# PWM_CONTROLLER_nverter_540VDC_V2.net
KiCad netlist of a schematic drawn in Altium Designer
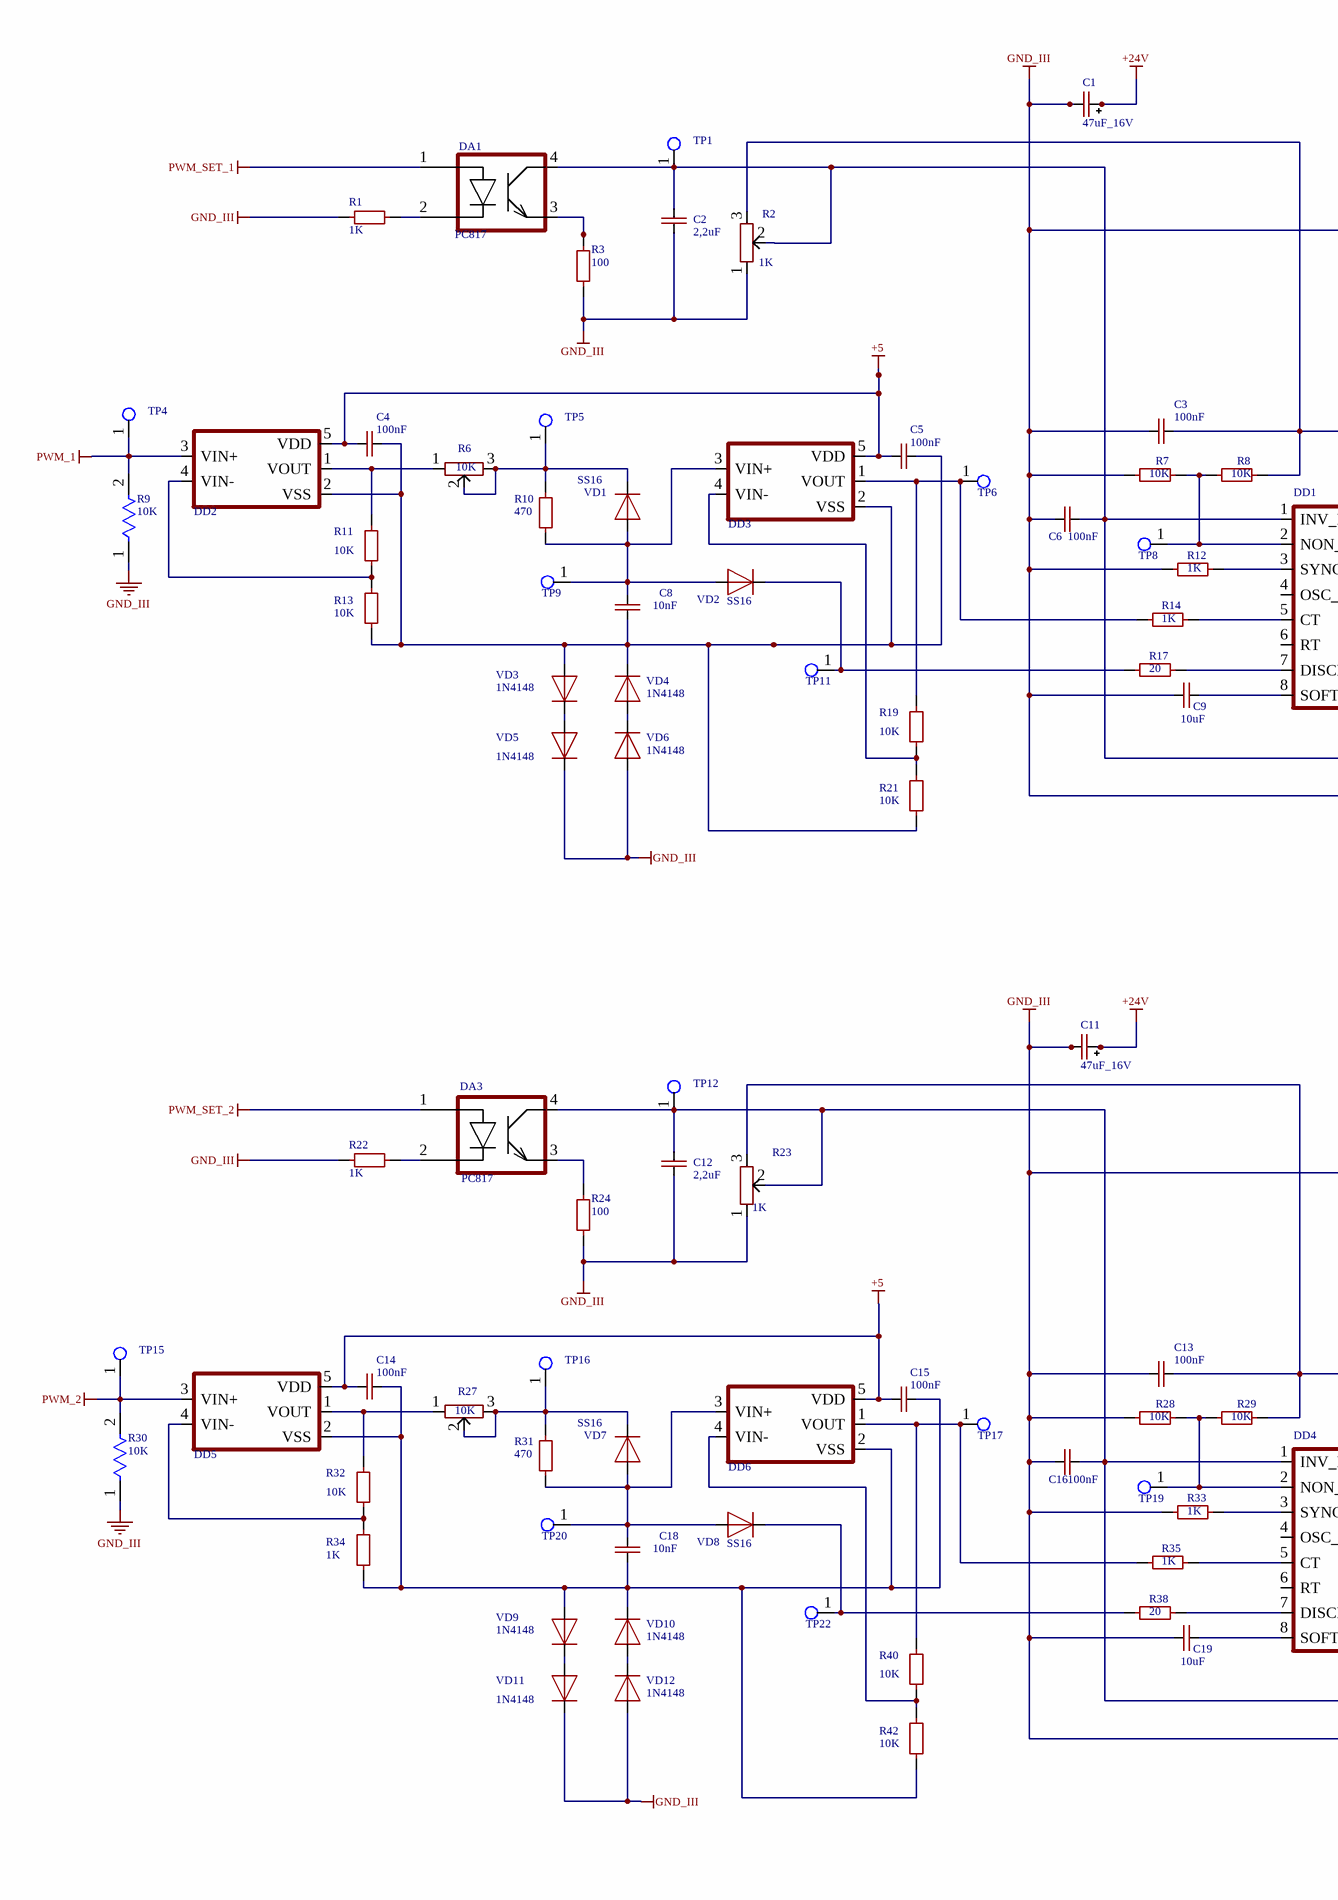
[diagram p0: PWM_CONTROLLER_nverter_540VDC_V2.SchDoc, top left]
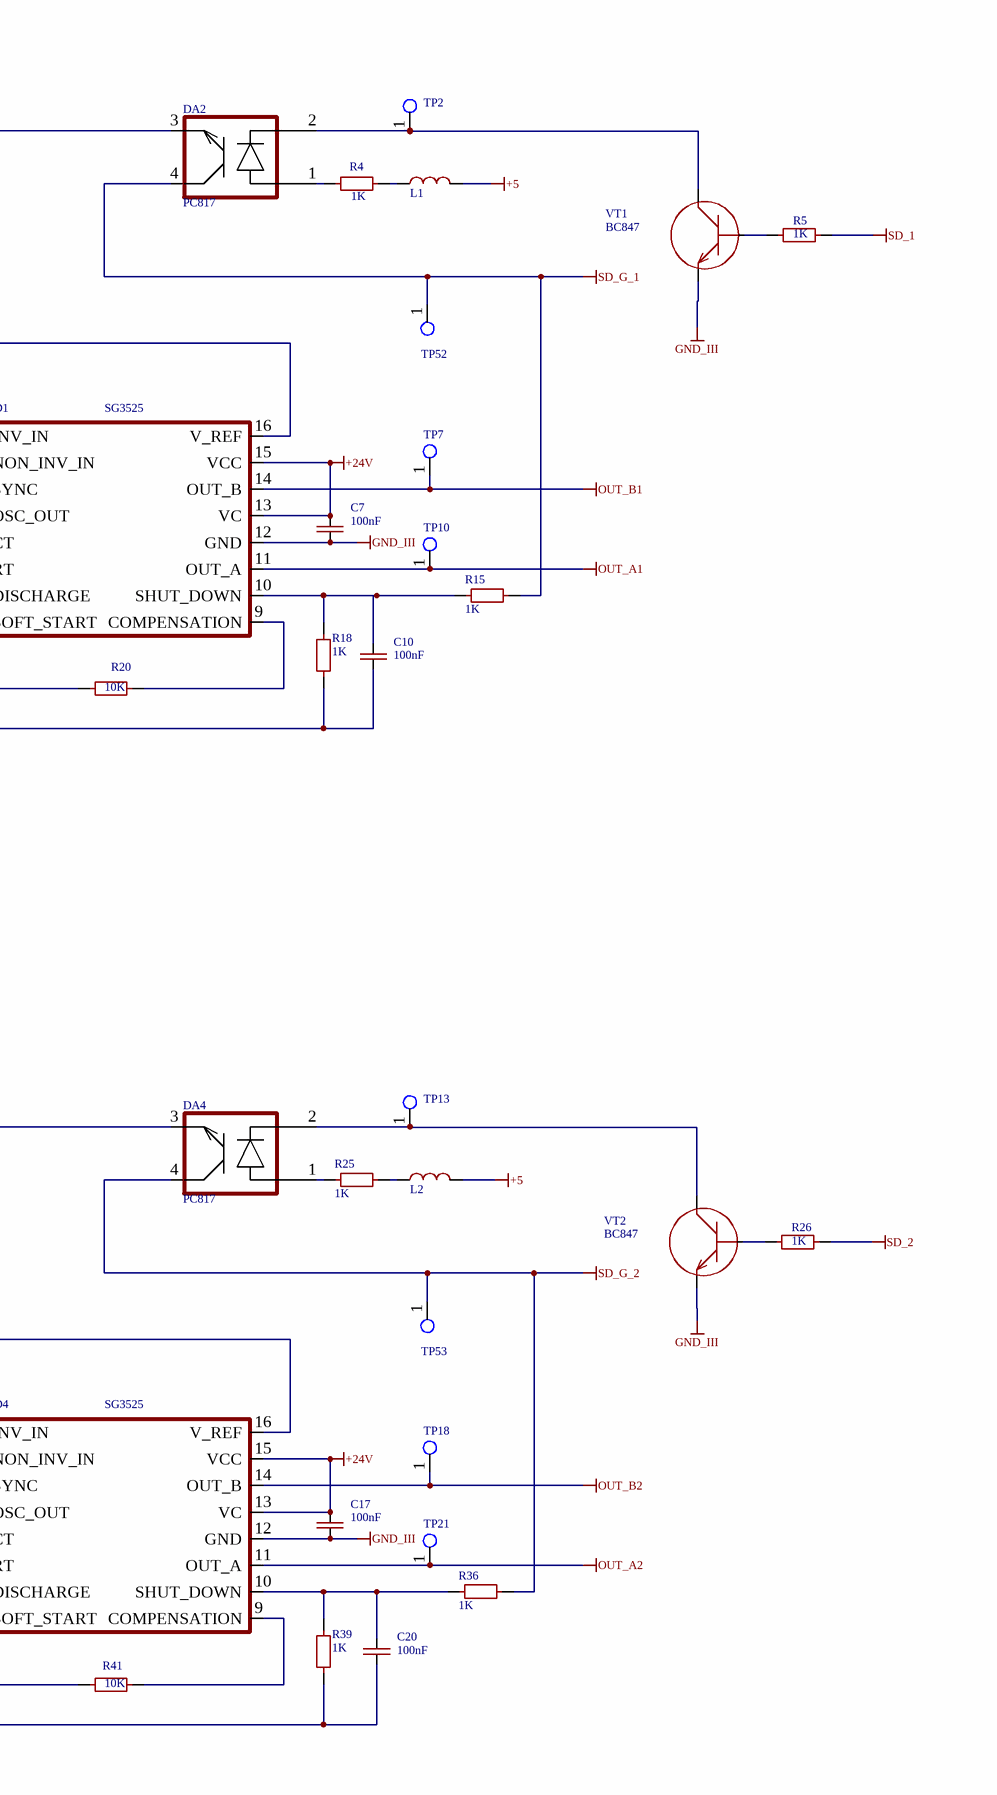
[diagram p1: PWM_CONTROLLER_nverter_540VDC_V2.SchDoc, top right]
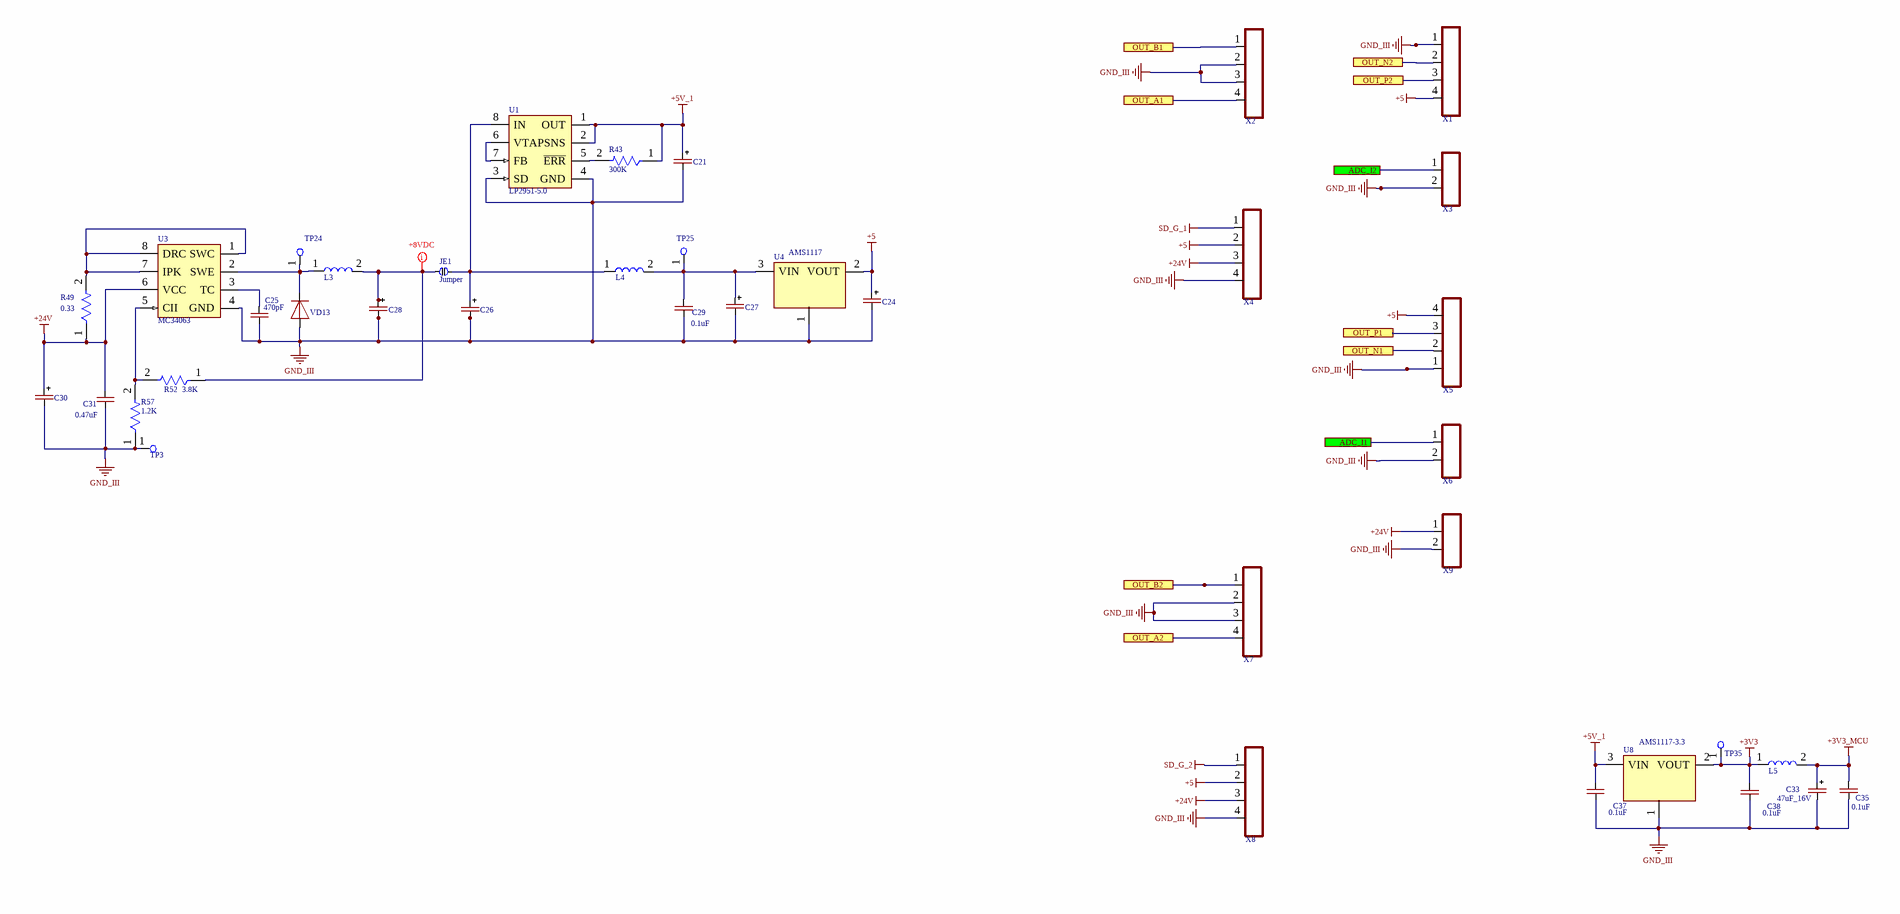
[diagram p2: PWM_CONTROLLER_nverter_540VDC_V2.SchDoc, bottom left]
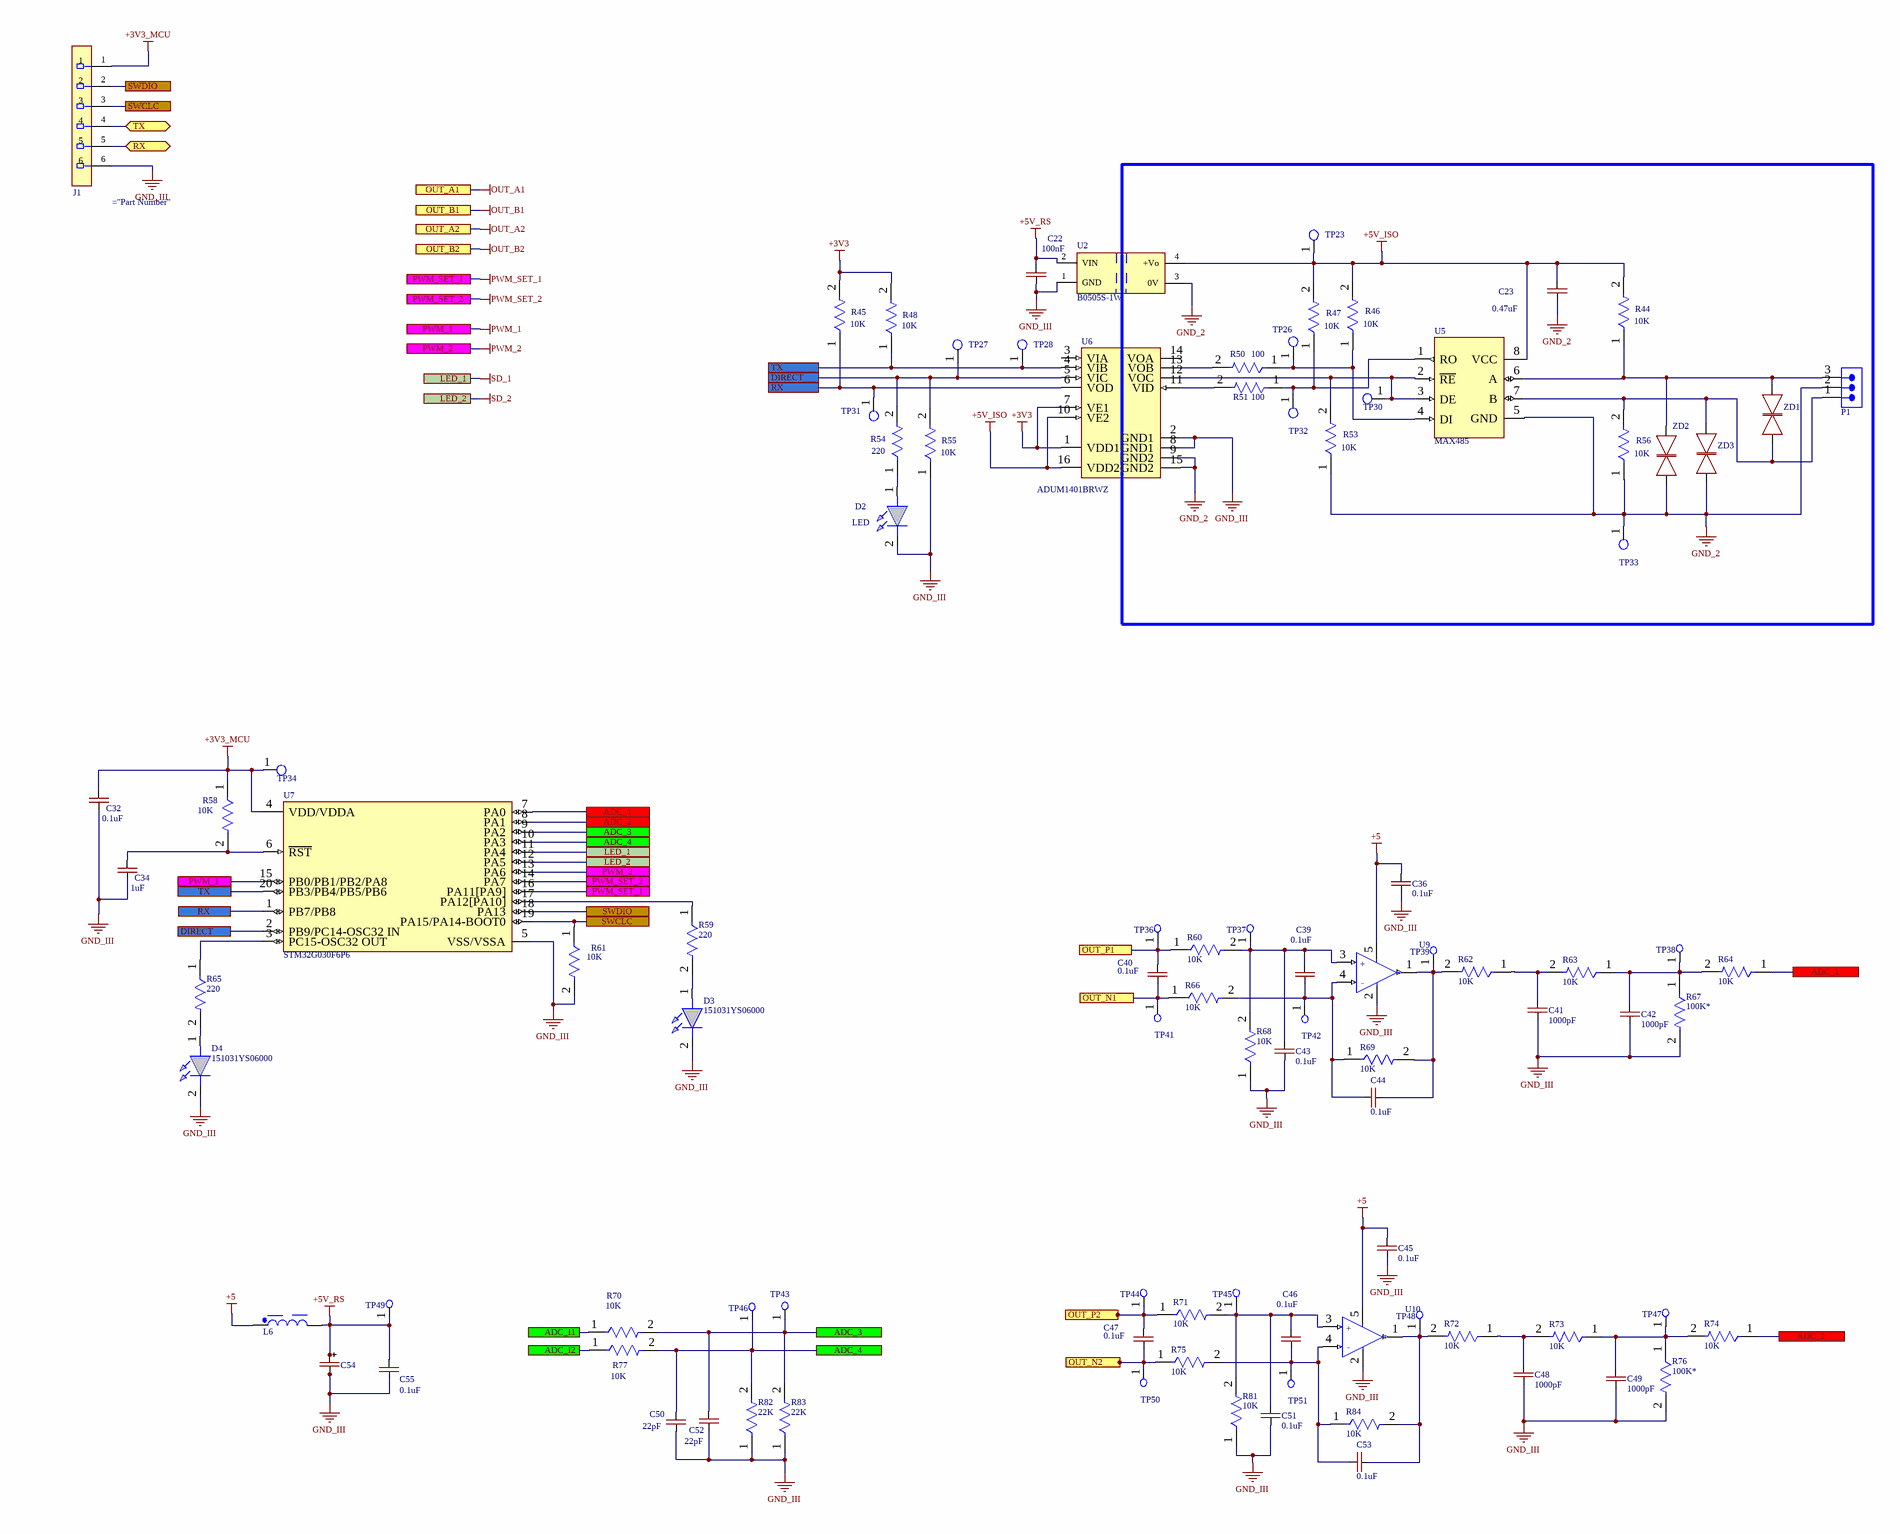
[diagram p3: PWM_CONTROLLER_nverter_540VDC_V2.SchDoc, bottom right]

(export (version "E")
  (design (tool "Eeschema 10.0.6"))
  (components
    (comp (ref "C1")
      (value "47uF_16V")
      (footprint "CAP-TAN-D")
      (libsource (lib "PASSIVE_COMPONENTS") (part "CAP-POLAR"))
    )
    (comp (ref "C2")
      (value "2,2uF")
      (footprint "CAP-0805")
      (libsource (lib "PAS_COMPONENTS") (part "CAP-NON-POLAR"))
    )
    (comp (ref "C3")
      (value "100nF")
      (footprint "CAP-0805")
      (libsource (lib "PAS_COMPONENTS") (part "CAP-NON-POLAR"))
    )
    (comp (ref "C4")
      (value "100nF")
      (footprint "CAP-0805")
      (libsource (lib "PAS_COMPONENTS") (part "CAP-NON-POLAR"))
    )
    (comp (ref "C5")
      (value "100nF")
      (footprint "CAP-0805")
      (libsource (lib "PAS_COMPONENTS") (part "CAP-NON-POLAR"))
    )
    (comp (ref "C6")
      (value "100nF")
      (footprint "CAP-0805")
      (libsource (lib "PAS_COMPONENTS") (part "CAP-NON-POLAR"))
    )
    (comp (ref "C7")
      (value "100nF")
      (footprint "CAP-0805")
      (libsource (lib "PAS_COMPONENTS") (part "CAP-NON-POLAR"))
    )
    (comp (ref "C8")
      (value "10nF")
      (footprint "CAP-0805")
      (libsource (lib "PAS_COMPONENTS") (part "CAP-NON-POLAR"))
    )
    (comp (ref "C9")
      (value "10uF")
      (footprint "CAP-0805")
      (libsource (lib "PAS_COMPONENTS") (part "CAP-NON-POLAR"))
    )
    (comp (ref "C10")
      (value "100nF")
      (footprint "CAP-0805")
      (libsource (lib "PAS_COMPONENTS") (part "CAP-NON-POLAR"))
    )
    (comp (ref "C11")
      (value "47uF_16V")
      (footprint "CAP-TAN-D")
      (libsource (lib "PASSIVE_COMPONENTS") (part "CAP-POLAR"))
    )
    (comp (ref "C12")
      (value "2,2uF")
      (footprint "CAP-0805")
      (libsource (lib "PAS_COMPONENTS") (part "CAP-NON-POLAR"))
    )
    (comp (ref "C13")
      (value "100nF")
      (footprint "CAP-0805")
      (libsource (lib "PAS_COMPONENTS") (part "CAP-NON-POLAR"))
    )
    (comp (ref "C14")
      (value "100nF")
      (footprint "CAP-0805")
      (libsource (lib "PAS_COMPONENTS") (part "CAP-NON-POLAR"))
    )
    (comp (ref "C15")
      (value "100nF")
      (footprint "CAP-0805")
      (libsource (lib "PAS_COMPONENTS") (part "CAP-NON-POLAR"))
    )
    (comp (ref "C16")
      (value "100nF")
      (footprint "CAP-0805")
      (libsource (lib "PAS_COMPONENTS") (part "CAP-NON-POLAR"))
    )
    (comp (ref "C17")
      (value "100nF")
      (footprint "CAP-0805")
      (libsource (lib "PAS_COMPONENTS") (part "CAP-NON-POLAR"))
    )
    (comp (ref "C18")
      (value "10nF")
      (footprint "CAP-0805")
      (libsource (lib "PAS_COMPONENTS") (part "CAP-NON-POLAR"))
    )
    (comp (ref "C19")
      (value "10uF")
      (footprint "CAP-0805")
      (libsource (lib "PAS_COMPONENTS") (part "CAP-NON-POLAR"))
    )
    (comp (ref "C20")
      (value "100nF")
      (footprint "CAP-0805")
      (libsource (lib "PAS_COMPONENTS") (part "CAP-NON-POLAR"))
    )
    (comp (ref "C21")
      (value "CAP-POLAR")
      (footprint "CAP-TAN-C")
      (libsource (lib "PAS_COMPONENTS") (part "CAP-POLAR"))
    )
    (comp (ref "C22")
      (value "100nF")
      (footprint "CAP-0805")
      (libsource (lib "PASSIVE_COMPONENTS") (part "CAP-NON-POLAR"))
    )
    (comp (ref "C23")
      (value "0.47uF")
      (footprint "CAP-0805")
      (libsource (lib "PASSIVE_COMPONENTS") (part "CAP-NON-POLAR"))
    )
    (comp (ref "C24")
      (value "CAP-POLAR")
      (footprint "CAP-TAN-C")
      (libsource (lib "PAS_COMPONENTS") (part "CAP-POLAR"))
    )
    (comp (ref "C25")
      (value "470pF")
      (footprint "CAP-0805")
      (libsource (lib "PASSIVE_COMPONENTS") (part "CAP-NON-POLAR"))
    )
    (comp (ref "C26")
      (value "CAP-POLAR")
      (footprint "CAP-TAN-C")
      (libsource (lib "PAS_COMPONENTS") (part "CAP-POLAR"))
    )
    (comp (ref "C27")
      (value "CAP-POLAR")
      (footprint "CAP-TAN-C")
      (libsource (lib "PAS_COMPONENTS") (part "CAP-POLAR"))
    )
    (comp (ref "C28")
      (value "CAP-POLAR")
      (footprint "CAP-TAN-C")
      (libsource (lib "PAS_COMPONENTS") (part "CAP-POLAR"))
    )
    (comp (ref "C29")
      (value "0.1uF")
      (footprint "CAP-0805")
      (libsource (lib "PASSIVE_COMPONENTS") (part "CAP-NON-POLAR"))
    )
    (comp (ref "C30")
      (value "CAP-POLAR")
      (footprint "CAP-TAN-C")
      (libsource (lib "PAS_COMPONENTS") (part "CAP-POLAR"))
    )
    (comp (ref "C31")
      (value "0.47uF")
      (footprint "CAP-0805")
      (libsource (lib "PASSIVE_COMPONENTS") (part "CAP-NON-POLAR"))
    )
    (comp (ref "C32")
      (value "0.1uF")
      (footprint "CAP-0805")
      (libsource (lib "PASSIVE_COMPONENTS") (part "CAP-NON-POLAR"))
    )
    (comp (ref "C33")
      (value "47uF_16V")
      (footprint "CAP-TAN-D")
      (libsource (lib "PASSIVE_COMPONENTS") (part "CAP-POLAR"))
    )
    (comp (ref "C34")
      (value "1uF")
      (footprint "CAP-0805")
      (libsource (lib "PASSIVE_COMPONENTS") (part "CAP-NON-POLAR"))
    )
    (comp (ref "C35")
      (value "0.1uF")
      (footprint "CAP-0805")
      (libsource (lib "PASSIVE_COMPONENTS") (part "CAP-NON-POLAR"))
    )
    (comp (ref "C36")
      (value "0.1uF")
      (footprint "CAP-0805")
      (libsource (lib "PASSIVE_COMPONENTS") (part "CAP-NON-POLAR"))
    )
    (comp (ref "C37")
      (value "0.1uF")
      (footprint "CAP-0805")
      (libsource (lib "PASSIVE_COMPONENTS") (part "CAP-NON-POLAR"))
    )
    (comp (ref "C38")
      (value "0.1uF")
      (footprint "CAP-0805")
      (libsource (lib "PASSIVE_COMPONENTS") (part "CAP-NON-POLAR"))
    )
    (comp (ref "C39")
      (value "0.1uF")
      (footprint "CAP-0805")
      (libsource (lib "PASSIVE_COMPONENTS") (part "CAP-NON-POLAR"))
    )
    (comp (ref "C40")
      (value "0.1uF")
      (footprint "CAP-0805")
      (libsource (lib "PASSIVE_COMPONENTS") (part "CAP-NON-POLAR"))
    )
    (comp (ref "C41")
      (value "1000pF")
      (footprint "CAP-0805")
      (libsource (lib "PASSIVE_COMPONENTS") (part "CAP-NON-POLAR"))
    )
    (comp (ref "C42")
      (value "1000pF")
      (footprint "CAP-0805")
      (libsource (lib "PASSIVE_COMPONENTS") (part "CAP-NON-POLAR"))
    )
    (comp (ref "C43")
      (value "0.1uF")
      (footprint "CAP-0805")
      (libsource (lib "PASSIVE_COMPONENTS") (part "CAP-NON-POLAR"))
    )
    (comp (ref "C44")
      (value "0.1uF")
      (footprint "CAP-0805")
      (libsource (lib "PASSIVE_COMPONENTS") (part "CAP-NON-POLAR"))
    )
    (comp (ref "C45")
      (value "0.1uF")
      (footprint "CAP-0805")
      (libsource (lib "PASSIVE_COMPONENTS") (part "CAP-NON-POLAR"))
    )
    (comp (ref "C46")
      (value "0.1uF")
      (footprint "CAP-0805")
      (libsource (lib "PASSIVE_COMPONENTS") (part "CAP-NON-POLAR"))
    )
    (comp (ref "C47")
      (value "0.1uF")
      (footprint "CAP-0805")
      (libsource (lib "PASSIVE_COMPONENTS") (part "CAP-NON-POLAR"))
    )
    (comp (ref "C48")
      (value "1000pF")
      (footprint "CAP-0805")
      (libsource (lib "PASSIVE_COMPONENTS") (part "CAP-NON-POLAR"))
    )
    (comp (ref "C49")
      (value "1000pF")
      (footprint "CAP-0805")
      (libsource (lib "PASSIVE_COMPONENTS") (part "CAP-NON-POLAR"))
    )
    (comp (ref "C50")
      (value "22pF")
      (footprint "CAP-0805")
      (libsource (lib "PASSIVE_COMPONENTS") (part "CAP-NON-POLAR"))
    )
    (comp (ref "C51")
      (value "0.1uF")
      (footprint "CAP-0805")
      (libsource (lib "PASSIVE_COMPONENTS") (part "CAP-NON-POLAR"))
    )
    (comp (ref "C52")
      (value "22pF")
      (footprint "CAP-0805")
      (libsource (lib "PASSIVE_COMPONENTS") (part "CAP-NON-POLAR"))
    )
    (comp (ref "C53")
      (value "0.1uF")
      (footprint "CAP-0805")
      (libsource (lib "PASSIVE_COMPONENTS") (part "CAP-NON-POLAR"))
    )
    (comp (ref "C54")
      (value "CAP-POLAR")
      (footprint "CAP-TAN-C")
      (libsource (lib "PAS_COMPONENTS") (part "CAP-POLAR"))
    )
    (comp (ref "C55")
      (value "0.1uF")
      (footprint "CAP-0805")
      (libsource (lib "PASSIVE_COMPONENTS") (part "CAP-NON-POLAR"))
    )
    (comp (ref "D2")
      (value "LED")
      (footprint "LED_RED")
      (description "WURTH ELEKTRONIK - 151031YS06000 - LED, Yellow, Through Hole, T-1 (3mm), 30 mA, 2 V, 590 nm")
      (fields
        (field (name "MANUFACTURER_PART_NUMBER") "151031YS06000")
        (field (name "MOUSER PART NUMBER") "710-151031YS06000")
      )
      (libsource (lib "Optic-LED") (part "LED"))
    )
    (comp (ref "D3")
      (value "151031YS06000")
      (footprint "LED_RED")
      (description "WURTH ELEKTRONIK - 151031YS06000 - LED, Yellow, Through Hole, T-1 (3mm), 30 mA, 2 V, 590 nm")
      (fields (field (name "MOUSER PART NUMBER") "710-151031YS06000"))
      (libsource (lib "Optic-LED") (part "LED"))
    )
    (comp (ref "D4")
      (value "151031YS06000")
      (footprint "LED_RED")
      (description "WURTH ELEKTRONIK - 151031YS06000 - LED, Yellow, Through Hole, T-1 (3mm), 30 mA, 2 V, 590 nm")
      (fields (field (name "MOUSER PART NUMBER") "710-151031YS06000"))
      (libsource (lib "Optic-LED") (part "LED"))
    )
    (comp (ref "DA1") (value "PC817") (footprint "4-SMD") (libsource (lib "PC817") (part "PC817")))
    (comp (ref "DA2") (value "PC817") (footprint "4-SMD") (libsource (lib "") (part "PC817_1")))
    (comp (ref "DA3") (value "PC817") (footprint "4-SMD") (libsource (lib "PC817") (part "PC817")))
    (comp (ref "DA4") (value "PC817") (footprint "4-SMD") (libsource (lib "") (part "PC817_1")))
    (comp (ref "DD1") (value "SG3525") (footprint "SO16-150") (libsource (lib "SG3525") (part "SG3525")))
    (comp (ref "DD2") (value "MCP6001") (footprint "SOT23-5") (libsource (lib "MCP6001") (part "MCP6001")))
    (comp (ref "DD3") (value "MCP6001") (footprint "SOT23-5") (libsource (lib "MCP6001") (part "MCP6001")))
    (comp (ref "DD4") (value "SG3525") (footprint "SO16-150") (libsource (lib "SG3525") (part "SG3525")))
    (comp (ref "DD5") (value "MCP6001") (footprint "SOT23-5") (libsource (lib "MCP6001") (part "MCP6001")))
    (comp (ref "DD6") (value "MCP6001") (footprint "SOT23-5") (libsource (lib "MCP6001") (part "MCP6001")))
    (comp (ref "J1")
      (value "SWR25X-NRTC-S06-ST-BA")
      (footprint "Sullins_SWR25X-NRTC-S06-ST-BA_MFG")
      (libsource (lib "Conn_Sullins_SWR25X-NRTC-S06-ST-BA_eec") (part "SWR25X-NRTC-S06-ST-BA"))
    )
    (comp (ref "JE1") (value "Jumper") (footprint "JE") (libsource (lib "Connectors") (part "JE")))
    (comp (ref "L1")
      (value "IND-CONST")
      (footprint "IND-5852")
      (libsource (lib "PAS_COMPONENTS") (part "IND-CONST"))
    )
    (comp (ref "L2")
      (value "IND-CONST")
      (footprint "IND-5852")
      (libsource (lib "PAS_COMPONENTS") (part "IND-CONST"))
    )
    (comp (ref "L3")
      (value "Coil")
      (footprint "Coil_4.5x4.5_mm")
      (libsource (lib "Transformers") (part "Coil"))
    )
    (comp (ref "L4")
      (value "Coil")
      (footprint "Coil_4.5x4.5_mm")
      (libsource (lib "Transformers") (part "Coil"))
    )
    (comp (ref "L5")
      (value "Coil")
      (footprint "Coil_4.5x4.5_mm")
      (libsource (lib "Transformers") (part "Coil"))
    )
    (comp (ref "L6")
      (value "1000µH, 0.3A")
      (footprint "WE-PD2_7850")
      (description "WE-PD2 SMT Power Inductor, size 7850, 1000µH, 0.3A, 3.3Ω")
      (fields
        (field (name "MANUFACTURER PART NUMBER") "74477530")
        (field (name "MANUFACTURER") "Wurth Elektronik")
      )
      (libsource (lib "WE-PD2 (rev22d)") (part "74477530"))
    )
    (comp (ref "P1")
      (value "691701530003B")
      (footprint "691701530003B")
      (description "WR-TBL Series 7015B Open Horizontal PCB Header, SMT, pitch 5.08mm, 3p")
      (fields (field (name "MANUFACTURER") "Wurth Elektronik"))
      (libsource (lib "Altium_WR-TBL (rev23d)") (part "691701530003B"))
    )
    (comp (ref "R1")
      (value "1K")
      (footprint "RES-0805")
      (description "10K")
      (libsource (lib "PAS_COMPONENTS") (part "RES-CONST"))
    )
    (comp (ref "R2") (value "1K") (footprint "3296W") (libsource (lib "3296") (part "3296")))
    (comp (ref "R3")
      (value "100")
      (footprint "RES-0805")
      (libsource (lib "PAS_COMPONENTS") (part "RES-CONST"))
    )
    (comp (ref "R4")
      (value "1K")
      (footprint "RES-0805")
      (libsource (lib "PAS_COMPONENTS") (part "RES-CONST"))
    )
    (comp (ref "R5")
      (value "1K")
      (footprint "RES-0805")
      (libsource (lib "PAS_COMPONENTS") (part "RES-CONST"))
    )
    (comp (ref "R6") (value "10K") (footprint "3296W") (libsource (lib "") (part "3296_1")))
    (comp (ref "R7")
      (value "10K")
      (footprint "RES-0805")
      (libsource (lib "PAS_COMPONENTS") (part "RES-CONST"))
    )
    (comp (ref "R8")
      (value "10K")
      (footprint "RES-0805")
      (libsource (lib "PAS_COMPONENTS") (part "RES-CONST"))
    )
    (comp (ref "R9")
      (value "10K")
      (footprint "RES-0805")
      (libsource (lib "PASSIVE_COMPONENTS") (part "RES-CONST"))
    )
    (comp (ref "R10")
      (value "470")
      (footprint "RES-0805")
      (libsource (lib "PAS_COMPONENTS") (part "RES-CONST"))
    )
    (comp (ref "R11")
      (value "10K")
      (footprint "RES-0805")
      (libsource (lib "PAS_COMPONENTS") (part "RES-CONST"))
    )
    (comp (ref "R12")
      (value "1K")
      (footprint "RES-0805")
      (libsource (lib "PAS_COMPONENTS") (part "RES-CONST"))
    )
    (comp (ref "R13")
      (value "10K")
      (footprint "RES-0805")
      (libsource (lib "PAS_COMPONENTS") (part "RES-CONST"))
    )
    (comp (ref "R14")
      (value "1K")
      (footprint "RES-0805")
      (libsource (lib "PAS_COMPONENTS") (part "RES-CONST"))
    )
    (comp (ref "R15")
      (value "1K")
      (footprint "RES-0805")
      (libsource (lib "PAS_COMPONENTS") (part "RES-CONST"))
    )
    (comp (ref "R17")
      (value "20")
      (footprint "RES-0805")
      (description "1K")
      (libsource (lib "PAS_COMPONENTS") (part "RES-CONST"))
    )
    (comp (ref "R18")
      (value "1K")
      (footprint "RES-0805")
      (libsource (lib "PAS_COMPONENTS") (part "RES-CONST"))
    )
    (comp (ref "R19")
      (value "10K")
      (footprint "RES-0805")
      (libsource (lib "PAS_COMPONENTS") (part "RES-CONST"))
    )
    (comp (ref "R20")
      (value "10K")
      (footprint "RES-0805")
      (libsource (lib "PAS_COMPONENTS") (part "RES-CONST"))
    )
    (comp (ref "R21")
      (value "10K")
      (footprint "RES-0805")
      (libsource (lib "PAS_COMPONENTS") (part "RES-CONST"))
    )
    (comp (ref "R22")
      (value "1K")
      (footprint "RES-0805")
      (description "10K")
      (libsource (lib "PAS_COMPONENTS") (part "RES-CONST"))
    )
    (comp (ref "R23") (value "1K") (footprint "3296W") (libsource (lib "3296W") (part "3296W")))
    (comp (ref "R24")
      (value "100")
      (footprint "RES-0805")
      (libsource (lib "PAS_COMPONENTS") (part "RES-CONST"))
    )
    (comp (ref "R25")
      (value "1K")
      (footprint "RES-0805")
      (libsource (lib "PAS_COMPONENTS") (part "RES-CONST"))
    )
    (comp (ref "R26")
      (value "1K")
      (footprint "RES-0805")
      (libsource (lib "PAS_COMPONENTS") (part "RES-CONST"))
    )
    (comp (ref "R27") (value "10K") (footprint "3296W") (libsource (lib "") (part "3296_1")))
    (comp (ref "R28")
      (value "10K")
      (footprint "RES-0805")
      (libsource (lib "PAS_COMPONENTS") (part "RES-CONST"))
    )
    (comp (ref "R29")
      (value "10K")
      (footprint "RES-0805")
      (libsource (lib "PAS_COMPONENTS") (part "RES-CONST"))
    )
    (comp (ref "R30")
      (value "10K")
      (footprint "RES-0805")
      (libsource (lib "PASSIVE_COMPONENTS") (part "RES-CONST"))
    )
    (comp (ref "R31")
      (value "470")
      (footprint "RES-0805")
      (libsource (lib "PAS_COMPONENTS") (part "RES-CONST"))
    )
    (comp (ref "R32")
      (value "10K")
      (footprint "RES-0805")
      (libsource (lib "PAS_COMPONENTS") (part "RES-CONST"))
    )
    (comp (ref "R33")
      (value "1K")
      (footprint "RES-0805")
      (libsource (lib "PAS_COMPONENTS") (part "RES-CONST"))
    )
    (comp (ref "R34")
      (value "1K")
      (footprint "RES-0805")
      (description "10K")
      (libsource (lib "PAS_COMPONENTS") (part "RES-CONST"))
    )
    (comp (ref "R35")
      (value "1K")
      (footprint "RES-0805")
      (libsource (lib "PAS_COMPONENTS") (part "RES-CONST"))
    )
    (comp (ref "R36")
      (value "1K")
      (footprint "RES-0805")
      (libsource (lib "PAS_COMPONENTS") (part "RES-CONST"))
    )
    (comp (ref "R38")
      (value "20")
      (footprint "RES-0805")
      (description "1K")
      (libsource (lib "PAS_COMPONENTS") (part "RES-CONST"))
    )
    (comp (ref "R39")
      (value "1K")
      (footprint "RES-0805")
      (libsource (lib "PAS_COMPONENTS") (part "RES-CONST"))
    )
    (comp (ref "R40")
      (value "10K")
      (footprint "RES-0805")
      (libsource (lib "PAS_COMPONENTS") (part "RES-CONST"))
    )
    (comp (ref "R41")
      (value "10K")
      (footprint "RES-0805")
      (libsource (lib "PAS_COMPONENTS") (part "RES-CONST"))
    )
    (comp (ref "R42")
      (value "10K")
      (footprint "RES-0805")
      (libsource (lib "PAS_COMPONENTS") (part "RES-CONST"))
    )
    (comp (ref "R43")
      (value "300K")
      (footprint "RES-0805")
      (libsource (lib "PASSIVE_COMPONENTS") (part "RES-CONST"))
    )
    (comp (ref "R44")
      (value "10K")
      (footprint "RES-0805")
      (libsource (lib "PASSIVE_COMPONENTS") (part "RES-CONST"))
    )
    (comp (ref "R45")
      (value "10K")
      (footprint "RES-0805")
      (libsource (lib "PASSIVE_COMPONENTS") (part "RES-CONST"))
    )
    (comp (ref "R46")
      (value "10K")
      (footprint "RES-0805")
      (libsource (lib "PASSIVE_COMPONENTS") (part "RES-CONST"))
    )
    (comp (ref "R47")
      (value "10K")
      (footprint "RES-0805")
      (libsource (lib "PASSIVE_COMPONENTS") (part "RES-CONST"))
    )
    (comp (ref "R48")
      (value "10K")
      (footprint "RES-0805")
      (libsource (lib "PASSIVE_COMPONENTS") (part "RES-CONST"))
    )
    (comp (ref "R49")
      (value "0.33")
      (footprint "RES-1206")
      (libsource (lib "PASSIVE_COMPONENTS") (part "RES-CONST"))
    )
    (comp (ref "R50")
      (value "100")
      (footprint "RES-0805")
      (libsource (lib "PASSIVE_COMPONENTS") (part "RES-CONST"))
    )
    (comp (ref "R51")
      (value "100")
      (footprint "RES-0805")
      (libsource (lib "PASSIVE_COMPONENTS") (part "RES-CONST"))
    )
    (comp (ref "R52")
      (value "3.8K")
      (footprint "RES-0805")
      (description "10K")
      (libsource (lib "PASSIVE_COMPONENTS") (part "RES-CONST"))
    )
    (comp (ref "R53")
      (value "10K")
      (footprint "RES-0805")
      (libsource (lib "PASSIVE_COMPONENTS") (part "RES-CONST"))
    )
    (comp (ref "R54")
      (value "220")
      (footprint "RES-0805")
      (libsource (lib "PASSIVE_COMPONENTS") (part "RES-CONST"))
    )
    (comp (ref "R55")
      (value "10K")
      (footprint "RES-0805")
      (libsource (lib "PASSIVE_COMPONENTS") (part "RES-CONST"))
    )
    (comp (ref "R56")
      (value "10K")
      (footprint "RES-0805")
      (libsource (lib "PASSIVE_COMPONENTS") (part "RES-CONST"))
    )
    (comp (ref "R57")
      (value "1.2K")
      (footprint "RES-0805")
      (libsource (lib "PASSIVE_COMPONENTS") (part "RES-CONST"))
    )
    (comp (ref "R58")
      (value "10K")
      (footprint "RES-0805")
      (libsource (lib "PASSIVE_COMPONENTS") (part "RES-CONST"))
    )
    (comp (ref "R59")
      (value "220")
      (footprint "RES-0805")
      (libsource (lib "PASSIVE_COMPONENTS") (part "RES-CONST"))
    )
    (comp (ref "R60")
      (value "10K")
      (footprint "RES-0805")
      (libsource (lib "PASSIVE_COMPONENTS") (part "RES-CONST"))
    )
    (comp (ref "R61")
      (value "10K")
      (footprint "RES-0805")
      (libsource (lib "PASSIVE_COMPONENTS") (part "RES-CONST"))
    )
    (comp (ref "R62")
      (value "10K")
      (footprint "RES-0805")
      (libsource (lib "PASSIVE_COMPONENTS") (part "RES-CONST"))
    )
    (comp (ref "R63")
      (value "10K")
      (footprint "RES-0805")
      (libsource (lib "PASSIVE_COMPONENTS") (part "RES-CONST"))
    )
    (comp (ref "R64")
      (value "10K")
      (footprint "RES-0805")
      (libsource (lib "PASSIVE_COMPONENTS") (part "RES-CONST"))
    )
    (comp (ref "R65")
      (value "220")
      (footprint "RES-0805")
      (libsource (lib "PASSIVE_COMPONENTS") (part "RES-CONST"))
    )
    (comp (ref "R66")
      (value "10K")
      (footprint "RES-0805")
      (libsource (lib "PASSIVE_COMPONENTS") (part "RES-CONST"))
    )
    (comp (ref "R67")
      (value "100K*")
      (footprint "RES-0805")
      (libsource (lib "PASSIVE_COMPONENTS") (part "RES-CONST"))
    )
    (comp (ref "R68")
      (value "10K")
      (footprint "RES-0805")
      (libsource (lib "PASSIVE_COMPONENTS") (part "RES-CONST"))
    )
    (comp (ref "R69")
      (value "10K")
      (footprint "RES-0805")
      (libsource (lib "PASSIVE_COMPONENTS") (part "RES-CONST"))
    )
    (comp (ref "R70")
      (value "10K")
      (footprint "RES-0805")
      (libsource (lib "PASSIVE_COMPONENTS") (part "RES-CONST"))
    )
    (comp (ref "R71")
      (value "10K")
      (footprint "RES-0805")
      (libsource (lib "PASSIVE_COMPONENTS") (part "RES-CONST"))
    )
    (comp (ref "R72")
      (value "10K")
      (footprint "RES-0805")
      (libsource (lib "PASSIVE_COMPONENTS") (part "RES-CONST"))
    )
    (comp (ref "R73")
      (value "10K")
      (footprint "RES-0805")
      (libsource (lib "PASSIVE_COMPONENTS") (part "RES-CONST"))
    )
    (comp (ref "R74")
      (value "10K")
      (footprint "RES-0805")
      (libsource (lib "PASSIVE_COMPONENTS") (part "RES-CONST"))
    )
    (comp (ref "R75")
      (value "10K")
      (footprint "RES-0805")
      (libsource (lib "PASSIVE_COMPONENTS") (part "RES-CONST"))
    )
    (comp (ref "R76")
      (value "100K*")
      (footprint "RES-0805")
      (libsource (lib "PASSIVE_COMPONENTS") (part "RES-CONST"))
    )
    (comp (ref "R77")
      (value "10K")
      (footprint "RES-0805")
      (libsource (lib "PASSIVE_COMPONENTS") (part "RES-CONST"))
    )
    (comp (ref "R81")
      (value "10K")
      (footprint "RES-0805")
      (libsource (lib "PASSIVE_COMPONENTS") (part "RES-CONST"))
    )
    (comp (ref "R82")
      (value "22K")
      (footprint "RES-0805")
      (libsource (lib "PASSIVE_COMPONENTS") (part "RES-CONST"))
    )
    (comp (ref "R83")
      (value "22K")
      (footprint "RES-0805")
      (libsource (lib "PASSIVE_COMPONENTS") (part "RES-CONST"))
    )
    (comp (ref "R84")
      (value "10K")
      (footprint "RES-0805")
      (libsource (lib "PASSIVE_COMPONENTS") (part "RES-CONST"))
    )
    (comp (ref "TP1")
      (value "Test_Point_PCB")
      (footprint "Test_Point")
      (description "Test_Point")
      (libsource (lib "TEST_POINT") (part "TP_PCB?"))
    )
    (comp (ref "TP2")
      (value "Test_Point_PCB")
      (footprint "Test_Point")
      (description "Test_Point")
      (libsource (lib "TEST_POINT") (part "TP_PCB?"))
    )
    (comp (ref "TP3")
      (value "Test_Point_PCB")
      (footprint "Test_Point")
      (description "Test_Point")
      (libsource (lib "Connectors") (part "TP_PCB?"))
    )
    (comp (ref "TP4")
      (value "Test_Point_PCB")
      (footprint "Test_Point")
      (description "Test_Point")
      (libsource (lib "TEST_POINT") (part "TP_PCB?"))
    )
    (comp (ref "TP5")
      (value "Test_Point_PCB")
      (footprint "Test_Point")
      (description "Test_Point")
      (libsource (lib "TEST_POINT") (part "TP_PCB?"))
    )
    (comp (ref "TP6")
      (value "Test_Point_PCB")
      (footprint "Test_Point")
      (description "Test_Point")
      (libsource (lib "TEST_POINT") (part "TP_PCB?"))
    )
    (comp (ref "TP7")
      (value "Test_Point_PCB")
      (footprint "Test_Point")
      (description "Test_Point")
      (libsource (lib "TEST_POINT") (part "TP_PCB?"))
    )
    (comp (ref "TP8")
      (value "Test_Point_PCB")
      (footprint "Test_Point")
      (description "Test_Point")
      (libsource (lib "TEST_POINT") (part "TP_PCB?"))
    )
    (comp (ref "TP9")
      (value "Test_Point_PCB")
      (footprint "Test_Point")
      (description "Test_Point")
      (libsource (lib "TEST_POINT") (part "TP_PCB?"))
    )
    (comp (ref "TP10")
      (value "Test_Point_PCB")
      (footprint "Test_Point")
      (description "Test_Point")
      (libsource (lib "TEST_POINT") (part "TP_PCB?"))
    )
    (comp (ref "TP11")
      (value "Test_Point_PCB")
      (footprint "Test_Point")
      (description "Test_Point")
      (libsource (lib "TEST_POINT") (part "TP_PCB?"))
    )
    (comp (ref "TP12")
      (value "Test_Point_PCB")
      (footprint "Test_Point")
      (description "Test_Point")
      (libsource (lib "TEST_POINT") (part "TP_PCB?"))
    )
    (comp (ref "TP13")
      (value "Test_Point_PCB")
      (footprint "Test_Point")
      (description "Test_Point")
      (libsource (lib "TEST_POINT") (part "TP_PCB?"))
    )
    (comp (ref "TP15")
      (value "Test_Point_PCB")
      (footprint "Test_Point")
      (description "Test_Point")
      (libsource (lib "TEST_POINT") (part "TP_PCB?"))
    )
    (comp (ref "TP16")
      (value "Test_Point_PCB")
      (footprint "Test_Point")
      (description "Test_Point")
      (libsource (lib "TEST_POINT") (part "TP_PCB?"))
    )
    (comp (ref "TP17")
      (value "Test_Point_PCB")
      (footprint "Test_Point")
      (description "Test_Point")
      (libsource (lib "TEST_POINT") (part "TP_PCB?"))
    )
    (comp (ref "TP18")
      (value "Test_Point_PCB")
      (footprint "Test_Point")
      (description "Test_Point")
      (libsource (lib "TEST_POINT") (part "TP_PCB?"))
    )
    (comp (ref "TP19")
      (value "Test_Point_PCB")
      (footprint "Test_Point")
      (description "Test_Point")
      (libsource (lib "TEST_POINT") (part "TP_PCB?"))
    )
    (comp (ref "TP20")
      (value "Test_Point_PCB")
      (footprint "Test_Point")
      (description "Test_Point")
      (libsource (lib "TEST_POINT") (part "TP_PCB?"))
    )
    (comp (ref "TP21")
      (value "Test_Point_PCB")
      (footprint "Test_Point")
      (description "Test_Point")
      (libsource (lib "TEST_POINT") (part "TP_PCB?"))
    )
    (comp (ref "TP22")
      (value "Test_Point_PCB")
      (footprint "Test_Point")
      (description "Test_Point")
      (libsource (lib "TEST_POINT") (part "TP_PCB?"))
    )
    (comp (ref "TP23")
      (value "Test_Point_PCB")
      (footprint "Test_Point")
      (description "Test_Point")
      (libsource (lib "Test_Point") (part "TP_PCB?"))
    )
    (comp (ref "TP24")
      (value "Test_Point_PCB")
      (footprint "Test_Point")
      (description "Test_Point")
      (libsource (lib "Connectors") (part "TP_PCB?"))
    )
    (comp (ref "TP25")
      (value "Test_Point_PCB")
      (footprint "Test_Point")
      (description "Test_Point")
      (libsource (lib "Connectors") (part "TP_PCB?"))
    )
    (comp (ref "TP26")
      (value "Test_Point_PCB")
      (footprint "Test_Point")
      (description "Test_Point")
      (libsource (lib "Test_Point") (part "TP_PCB?"))
    )
    (comp (ref "TP27")
      (value "Test_Point_PCB")
      (footprint "Test_Point")
      (description "Test_Point")
      (libsource (lib "Test_Point") (part "TP_PCB?"))
    )
    (comp (ref "TP28")
      (value "Test_Point_PCB")
      (footprint "Test_Point")
      (description "Test_Point")
      (libsource (lib "Test_Point") (part "TP_PCB?"))
    )
    (comp (ref "TP30")
      (value "Test_Point_PCB")
      (footprint "Test_Point")
      (description "Test_Point")
      (libsource (lib "Test_Point") (part "TP_PCB?"))
    )
    (comp (ref "TP31")
      (value "Test_Point_PCB")
      (footprint "Test_Point")
      (description "Test_Point")
      (libsource (lib "Test_Point") (part "TP_PCB?"))
    )
    (comp (ref "TP32")
      (value "~")
      (footprint "Test_Point")
      (description "Test_Point")
      (libsource (lib "") (part "TP_PCB?_1"))
    )
    (comp (ref "TP33")
      (value "Test_Point_PCB")
      (footprint "Test_Point")
      (description "Test_Point")
      (libsource (lib "Test_Point") (part "TP_PCB?"))
    )
    (comp (ref "TP34")
      (value "~")
      (footprint "Test_Point")
      (description "Test_Point")
      (libsource (lib "") (part "TP_PCB?_1"))
    )
    (comp (ref "TP35")
      (value "Test_Point_PCB")
      (footprint "Test_Point")
      (description "Test_Point")
      (libsource (lib "Connectors") (part "TP_PCB?"))
    )
    (comp (ref "TP36")
      (value "Test_Point_PCB")
      (footprint "Test_Point")
      (description "Test_Point")
      (libsource (lib "Connectors") (part "TP_PCB?"))
    )
    (comp (ref "TP37")
      (value "Test_Point_PCB")
      (footprint "Test_Point")
      (description "Test_Point")
      (libsource (lib "Connectors") (part "TP_PCB?"))
    )
    (comp (ref "TP38")
      (value "Test_Point_PCB")
      (footprint "Test_Point")
      (description "Test_Point")
      (libsource (lib "Connectors") (part "TP_PCB?"))
    )
    (comp (ref "TP39")
      (value "Test_Point_PCB")
      (footprint "Test_Point")
      (description "Test_Point")
      (libsource (lib "Connectors") (part "TP_PCB?"))
    )
    (comp (ref "TP41")
      (value "Test_Point_PCB")
      (footprint "Test_Point")
      (description "Test_Point")
      (libsource (lib "Connectors") (part "TP_PCB?"))
    )
    (comp (ref "TP42")
      (value "Test_Point_PCB")
      (footprint "Test_Point")
      (description "Test_Point")
      (libsource (lib "Connectors") (part "TP_PCB?"))
    )
    (comp (ref "TP43")
      (value "Test_Point_PCB")
      (footprint "Test_Point")
      (description "Test_Point")
      (libsource (lib "Connectors") (part "TP_PCB?"))
    )
    (comp (ref "TP44")
      (value "Test_Point_PCB")
      (footprint "Test_Point")
      (description "Test_Point")
      (libsource (lib "Connectors") (part "TP_PCB?"))
    )
    (comp (ref "TP45")
      (value "Test_Point_PCB")
      (footprint "Test_Point")
      (description "Test_Point")
      (libsource (lib "Connectors") (part "TP_PCB?"))
    )
    (comp (ref "TP46")
      (value "Test_Point_PCB")
      (footprint "Test_Point")
      (description "Test_Point")
      (libsource (lib "Connectors") (part "TP_PCB?"))
    )
    (comp (ref "TP47")
      (value "Test_Point_PCB")
      (footprint "Test_Point")
      (description "Test_Point")
      (libsource (lib "Connectors") (part "TP_PCB?"))
    )
    (comp (ref "TP48")
      (value "Test_Point_PCB")
      (footprint "Test_Point")
      (description "Test_Point")
      (libsource (lib "Connectors") (part "TP_PCB?"))
    )
    (comp (ref "TP49")
      (value "Test_Point_PCB")
      (footprint "Test_Point")
      (description "Test_Point")
      (libsource (lib "Connectors") (part "TP_PCB?"))
    )
    (comp (ref "TP50")
      (value "Test_Point_PCB")
      (footprint "Test_Point")
      (description "Test_Point")
      (libsource (lib "Connectors") (part "TP_PCB?"))
    )
    (comp (ref "TP51")
      (value "Test_Point_PCB")
      (footprint "Test_Point")
      (description "Test_Point")
      (libsource (lib "Connectors") (part "TP_PCB?"))
    )
    (comp (ref "TP52")
      (value "Test_Point_PCB")
      (footprint "Test_Point")
      (description "Test_Point")
      (libsource (lib "TEST_POINT") (part "TP_PCB?"))
    )
    (comp (ref "TP53")
      (value "Test_Point_PCB")
      (footprint "Test_Point")
      (description "Test_Point")
      (libsource (lib "TEST_POINT") (part "TP_PCB?"))
    )
    (comp (ref "U1")
      (value "LP2951-5.0")
      (footprint "SOIC-8_L")
      (libsource (lib "Integrated_Circuts") (part "LP2951-3.3"))
    )
    (comp (ref "U2")
      (value "B0505S-1W")
      (footprint "B0505S-1W")
      (libsource (lib "Integrated_Circuts") (part "B0505S-1W"))
    )
    (comp (ref "U3")
      (value "MC34063")
      (footprint "SOIC-8_M")
      (libsource (lib "Integrated_Circuts") (part "MC34063"))
    )
    (comp (ref "U4")
      (value "AMS1117")
      (footprint "SOT-89")
      (libsource (lib "Integrated_Circuts") (part "AMS1117"))
    )
    (comp (ref "U5")
      (value "MAX485")
      (footprint "SOIC-8-MFG")
      (libsource (lib "Integrated_Circuts") (part "MAX485"))
    )
    (comp (ref "U6")
      (value "ADUM1401BRWZ")
      (footprint "ADI-RW-16_M")
      (fields (field (name "MANUFACTURER") "Analog Devices"))
      (libsource (lib "Altium Content Vault") (part "ADI-ADUMX4X1-16"))
    )
    (comp (ref "U7")
      (value "STM32G030F6P6")
      (footprint "FP-TSSOP20-YA-IPC_A")
      (description "SOIC-20")
      (libsource (lib "Integrated_Circuts") (part "STM32G030F6P6"))
    )
    (comp (ref "U8")
      (value "AMS1117-3.3")
      (footprint "SOT-223")
      (libsource (lib "Integrated_Circuts") (part "AMS1117"))
    )
    (comp (ref "U9")
      (value "~")
      (footprint "SOT-23-5")
      (description "IC OPAMP GP 1 CIRCUIT SOT23-5")
      (fields (field (name "VOLTAGE") "6V"))
      (libsource (lib "Integrated_Circuts") (part "MCP6001T"))
    )
    (comp (ref "U10")
      (value "~")
      (footprint "SOT-23-5")
      (description "IC OPAMP GP 1 CIRCUIT SOT23-5")
      (fields (field (name "VOLTAGE") "6V"))
      (libsource (lib "Integrated_Circuts") (part "MCP6001T"))
    )
    (comp (ref "VD1") (value "SS16") (footprint "DO-214AC, SMA") (libsource (lib "DIODES") (part "DIODE")))
    (comp (ref "VD2") (value "SS16") (footprint "DO-214AC, SMA") (libsource (lib "DIODES") (part "DIODE")))
    (comp (ref "VD3") (value "1N4148") (footprint "SOD-123") (libsource (lib "DIODES") (part "DIODE")))
    (comp (ref "VD4") (value "1N4148") (footprint "SOD-123") (libsource (lib "DIODES") (part "DIODE")))
    (comp (ref "VD5") (value "1N4148") (footprint "SOD-123") (libsource (lib "DIODES") (part "DIODE")))
    (comp (ref "VD6") (value "1N4148") (footprint "SOD-123") (libsource (lib "DIODES") (part "DIODE")))
    (comp (ref "VD7") (value "SS16") (footprint "DO-214AC, SMA") (libsource (lib "DIODES") (part "DIODE")))
    (comp (ref "VD8") (value "SS16") (footprint "DO-214AC, SMA") (libsource (lib "DIODES") (part "DIODE")))
    (comp (ref "VD9") (value "1N4148") (footprint "SOD-123") (libsource (lib "DIODES") (part "DIODE")))
    (comp (ref "VD10") (value "1N4148") (footprint "SOD-123") (libsource (lib "DIODES") (part "DIODE")))
    (comp (ref "VD11") (value "1N4148") (footprint "SOD-123") (libsource (lib "DIODES") (part "DIODE")))
    (comp (ref "VD12") (value "1N4148") (footprint "SOD-123") (libsource (lib "DIODES") (part "DIODE")))
    (comp (ref "VD13") (value "DIODE") (footprint "DO-214AC, SMA") (libsource (lib "DIODES") (part "DIODE")))
    (comp (ref "VT1")
      (value "BC847")
      (footprint "SOT23-3")
      (libsource (lib "TRANSISTORS") (part "BIPOLAR-NPN-BEC"))
    )
    (comp (ref "VT2")
      (value "BC847")
      (footprint "SOT23-3")
      (libsource (lib "TRANSISTORS") (part "BIPOLAR-NPN-BEC"))
    )
    (comp (ref "X1")
      (value "CONN-4-PIN")
      (footprint "CONN-PLS-4-2.54mm_1")
      (libsource (lib "XH 4PIN") (part "CONN-4-PIN"))
    )
    (comp (ref "X2")
      (value "CONN-4-PIN")
      (footprint "CONN-PLS-4-2.54mm_1")
      (libsource (lib "XH 4PIN") (part "CONN-4-PIN"))
    )
    (comp (ref "X3") (value "CONN-2-PIN") (footprint "XH2-") (libsource (lib "XH 2PIN") (part "CONN-2-PIN")))
    (comp (ref "X4")
      (value "CONN-4-PIN")
      (footprint "CONN-PLS-4-2.54mm_1")
      (libsource (lib "XH 4PIN") (part "CONN-4-PIN"))
    )
    (comp (ref "X5")
      (value "CONN-4-PIN")
      (footprint "CONN-PLS-4-2.54mm_1")
      (libsource (lib "") (part "CONN-4-PIN_1"))
    )
    (comp (ref "X6") (value "CONN-2-PIN") (footprint "XH2-") (libsource (lib "XH 2PIN") (part "CONN-2-PIN")))
    (comp (ref "X7")
      (value "CONN-4-PIN")
      (footprint "CONN-PLS-4-2.54mm_1")
      (libsource (lib "XH 4PIN") (part "CONN-4-PIN"))
    )
    (comp (ref "X8")
      (value "CONN-4-PIN")
      (footprint "CONN-PLS-4-2.54mm_1")
      (libsource (lib "XH 4PIN") (part "CONN-4-PIN"))
    )
    (comp (ref "X9") (value "CONN-2-PIN") (footprint "XH2-") (libsource (lib "XH 2PIN") (part "CONN-2-PIN")))
    (comp (ref "ZD1")
      (value "P6SMB16CA")
      (footprint "DO-214AA")
      (libsource (lib "P6SMB16CA") (part "P6SMB16CA"))
    )
    (comp (ref "ZD2")
      (value "P6SMB16CA")
      (footprint "DO-214AA")
      (libsource (lib "P6SMB16CA") (part "P6SMB16CA"))
    )
    (comp (ref "ZD3")
      (value "P6SMB16CA")
      (footprint "DO-214AA")
      (libsource (lib "P6SMB16CA") (part "P6SMB16CA"))
    )
  )
  (nets
    (net (code "1") (name "+3V3") (class "Default")
      (node (ref "C38") (pin "2") (pinfunction "2_2") (pintype "passive"))
      (node (ref "L5") (pin "1") (pinfunction "1_1") (pintype "passive"))
      (node (ref "R45") (pin "2") (pinfunction "2_2") (pintype "passive"))
      (node (ref "R48") (pin "2") (pinfunction "2_2") (pintype "passive"))
      (node (ref "TP35") (pin "1") (pinfunction "G9_1") (pintype "passive"))
      (node (ref "U6") (pin "1") (pinfunction "VDD1_1") (pintype "power_in"))
      (node (ref "U6") (pin "7") (pinfunction "VE1_7") (pintype "input"))
      (node (ref "U8") (pin "2") (pinfunction "VOUT_2") (pintype "passive"))
    )
    (net (code "2") (name "+3V3_MCU") (class "Default")
      (node (ref "C32") (pin "2") (pinfunction "2_2") (pintype "passive"))
      (node (ref "C33") (pin "1") (pinfunction "+_1") (pintype "passive"))
      (node (ref "C35") (pin "2") (pinfunction "2_2") (pintype "passive"))
      (node (ref "J1") (pin "1") (pinfunction "1_1") (pintype "passive"))
      (node (ref "L5") (pin "2") (pinfunction "2_2") (pintype "passive"))
      (node (ref "R58") (pin "1") (pinfunction "1_1") (pintype "passive"))
      (node (ref "TP34") (pin "1") (pinfunction "G9_1") (pintype "passive"))
      (node (ref "U7") (pin "4") (pinfunction "VDD/VDDA_4") (pintype "power_in"))
    )
    (net (code "3") (name "+5") (class "Default")
      (node (ref "C14") (pin "2") (pinfunction "2_2") (pintype "passive"))
      (node (ref "C15") (pin "2") (pinfunction "2_2") (pintype "passive"))
      (node (ref "C24") (pin "1") (pinfunction "+_1") (pintype "passive"))
      (node (ref "C36") (pin "2") (pinfunction "2_2") (pintype "passive"))
      (node (ref "C4") (pin "2") (pinfunction "2_2") (pintype "passive"))
      (node (ref "C45") (pin "2") (pinfunction "2_2") (pintype "passive"))
      (node (ref "C5") (pin "2") (pinfunction "2_2") (pintype "passive"))
      (node (ref "DD2") (pin "5") (pinfunction "VDD_5") (pintype "passive"))
      (node (ref "DD3") (pin "5") (pinfunction "VDD_5") (pintype "passive"))
      (node (ref "DD5") (pin "5") (pinfunction "VDD_5") (pintype "passive"))
      (node (ref "DD6") (pin "5") (pinfunction "VDD_5") (pintype "passive"))
      (node (ref "L1") (pin "2") (pinfunction "2_2") (pintype "passive"))
      (node (ref "L2") (pin "2") (pinfunction "2_2") (pintype "passive"))
      (node (ref "L6") (pin "1") (pinfunction "1_1") (pintype "passive"))
      (node (ref "U10") (pin "5") (pinfunction "VDD_5") (pintype "power_in"))
      (node (ref "U4") (pin "2") (pinfunction "VOUT_2") (pintype "passive"))
      (node (ref "U9") (pin "5") (pinfunction "VDD_5") (pintype "power_in"))
      (node (ref "X1") (pin "4") (pinfunction "4_4") (pintype "passive"))
      (node (ref "X4") (pin "2") (pinfunction "2_2") (pintype "passive"))
      (node (ref "X5") (pin "4") (pinfunction "4_4") (pintype "passive"))
      (node (ref "X8") (pin "2") (pinfunction "2_2") (pintype "passive"))
    )
    (net (code "4") (name "+5V_1") (class "Default")
      (node (ref "C21") (pin "1") (pinfunction "+_1") (pintype "passive"))
      (node (ref "C37") (pin "2") (pinfunction "2_2") (pintype "passive"))
      (node (ref "R43") (pin "1") (pinfunction "1_1") (pintype "passive"))
      (node (ref "U1") (pin "1") (pinfunction "OUT_1") (pintype "power_in"))
      (node (ref "U1") (pin "2") (pinfunction "SNS_2") (pintype "passive"))
      (node (ref "U8") (pin "3") (pinfunction "VIN_3") (pintype "power_in"))
    )
    (net (code "5") (name "+5V_ISO") (class "Default")
      (node (ref "C23") (pin "1") (pinfunction "1_1") (pintype "passive"))
      (node (ref "R44") (pin "2") (pinfunction "2_2") (pintype "passive"))
      (node (ref "R46") (pin "2") (pinfunction "2_2") (pintype "passive"))
      (node (ref "R47") (pin "2") (pinfunction "2_2") (pintype "passive"))
      (node (ref "TP23") (pin "1") (pinfunction "G9_1") (pintype "passive"))
      (node (ref "U2") (pin "4") (pinfunction "+Vo_4") (pintype "power_in"))
      (node (ref "U5") (pin "8") (pinfunction "VCC_8") (pintype "power_in"))
      (node (ref "U6") (pin "10") (pinfunction "VE2_10") (pintype "input"))
      (node (ref "U6") (pin "16") (pinfunction "VDD2_16") (pintype "power_in"))
    )
    (net (code "6") (name "+5V_RS") (class "Default")
      (node (ref "C22") (pin "2") (pinfunction "2_2") (pintype "passive"))
      (node (ref "C54") (pin "1") (pinfunction "+_1") (pintype "passive"))
      (node (ref "C55") (pin "2") (pinfunction "2_2") (pintype "passive"))
      (node (ref "L6") (pin "2") (pinfunction "2_2") (pintype "passive"))
      (node (ref "TP49") (pin "1") (pinfunction "G9_1") (pintype "passive"))
      (node (ref "U2") (pin "2") (pinfunction "VIN_2") (pintype "power_in"))
    )
    (net (code "7") (name "+24V") (class "Default")
      (node (ref "C1") (pin "1") (pinfunction "+_1") (pintype "passive"))
      (node (ref "C11") (pin "1") (pinfunction "+_1") (pintype "passive"))
      (node (ref "C17") (pin "2") (pinfunction "2_2") (pintype "passive"))
      (node (ref "C30") (pin "1") (pinfunction "+_1") (pintype "passive"))
      (node (ref "C31") (pin "1") (pinfunction "1_1") (pintype "passive"))
      (node (ref "C7") (pin "2") (pinfunction "2_2") (pintype "passive"))
      (node (ref "DD1") (pin "13") (pinfunction "VC_13") (pintype "passive"))
      (node (ref "DD1") (pin "15") (pinfunction "VCC_15") (pintype "passive"))
      (node (ref "DD4") (pin "13") (pinfunction "VC_13") (pintype "passive"))
      (node (ref "DD4") (pin "15") (pinfunction "VCC_15") (pintype "passive"))
      (node (ref "R49") (pin "1") (pinfunction "1_1") (pintype "passive"))
      (node (ref "U3") (pin "6") (pinfunction "VCC_6") (pintype "power_in"))
      (node (ref "X4") (pin "3") (pinfunction "3_3") (pintype "passive"))
      (node (ref "X8") (pin "3") (pinfunction "3_3") (pintype "passive"))
      (node (ref "X9") (pin "1") (pinfunction "1_1") (pintype "passive"))
    )
    (net (code "8") (name "/ADC_1") (class "Default")
      (node (ref "R64") (pin "1") (pinfunction "1_1") (pintype "passive"))
      (node (ref "U7") (pin "7") (pinfunction "PA0_7") (pintype "bidirectional"))
    )
    (net (code "9") (name "/ADC_2") (class "Default")
      (node (ref "R74") (pin "1") (pinfunction "1_1") (pintype "passive"))
      (node (ref "U7") (pin "8") (pinfunction "PA1_8") (pintype "bidirectional"))
    )
    (net (code "10") (name "/ADC_3") (class "Default")
      (node (ref "C52") (pin "2") (pinfunction "2_2") (pintype "passive"))
      (node (ref "R70") (pin "2") (pinfunction "2_2") (pintype "passive"))
      (node (ref "R83") (pin "2") (pinfunction "2_2") (pintype "passive"))
      (node (ref "TP43") (pin "1") (pinfunction "G9_1") (pintype "passive"))
      (node (ref "U7") (pin "9") (pinfunction "PA2_9") (pintype "bidirectional"))
    )
    (net (code "11") (name "/ADC_4") (class "Default")
      (node (ref "C50") (pin "2") (pinfunction "2_2") (pintype "passive"))
      (node (ref "R77") (pin "2") (pinfunction "2_2") (pintype "passive"))
      (node (ref "R82") (pin "2") (pinfunction "2_2") (pintype "passive"))
      (node (ref "TP46") (pin "1") (pinfunction "G9_1") (pintype "passive"))
      (node (ref "U7") (pin "10") (pinfunction "PA3_10") (pintype "bidirectional"))
    )
    (net (code "12") (name "/ADC_I1") (class "Default")
      (node (ref "R70") (pin "1") (pinfunction "1_1") (pintype "passive"))
      (node (ref "X6") (pin "1") (pinfunction "1_1") (pintype "passive"))
    )
    (net (code "13") (name "/ADC_I2") (class "Default")
      (node (ref "R77") (pin "1") (pinfunction "1_1") (pintype "passive"))
      (node (ref "X3") (pin "1") (pinfunction "1_1") (pintype "passive"))
    )
    (net (code "14") (name "/DIRECT") (class "Default")
      (node (ref "R54") (pin "2") (pinfunction "2_2") (pintype "passive"))
      (node (ref "R55") (pin "2") (pinfunction "2_2") (pintype "passive"))
      (node (ref "TP27") (pin "1") (pinfunction "G9_1") (pintype "passive"))
      (node (ref "U6") (pin "5") (pinfunction "VIC_5") (pintype "input"))
      (node (ref "U7") (pin "2") (pinfunction "PB9/PC14-OSC32_IN_2") (pintype "bidirectional"))
    )
    (net (code "15") (name "/OUT_N1") (class "Default")
      (node (ref "C40") (pin "1") (pinfunction "1_1") (pintype "passive"))
      (node (ref "R66") (pin "1") (pinfunction "1_1") (pintype "passive"))
      (node (ref "TP41") (pin "1") (pinfunction "G9_1") (pintype "passive"))
      (node (ref "X5") (pin "2") (pinfunction "2_2") (pintype "passive"))
    )
    (net (code "16") (name "/OUT_N2") (class "Default")
      (node (ref "C47") (pin "1") (pinfunction "1_1") (pintype "passive"))
      (node (ref "R75") (pin "1") (pinfunction "1_1") (pintype "passive"))
      (node (ref "TP50") (pin "1") (pinfunction "G9_1") (pintype "passive"))
      (node (ref "X1") (pin "2") (pinfunction "2_2") (pintype "passive"))
    )
    (net (code "17") (name "/OUT_P1") (class "Default")
      (node (ref "C40") (pin "2") (pinfunction "2_2") (pintype "passive"))
      (node (ref "R60") (pin "1") (pinfunction "1_1") (pintype "passive"))
      (node (ref "TP36") (pin "1") (pinfunction "G9_1") (pintype "passive"))
      (node (ref "X5") (pin "3") (pinfunction "3_3") (pintype "passive"))
    )
    (net (code "18") (name "/OUT_P2") (class "Default")
      (node (ref "C47") (pin "2") (pinfunction "2_2") (pintype "passive"))
      (node (ref "R71") (pin "1") (pinfunction "1_1") (pintype "passive"))
      (node (ref "TP44") (pin "1") (pinfunction "G9_1") (pintype "passive"))
      (node (ref "X1") (pin "3") (pinfunction "3_3") (pintype "passive"))
    )
    (net (code "19") (name "/RX") (class "Default")
      (node (ref "J1") (pin "5") (pinfunction "5_5") (pintype "passive"))
      (node (ref "R45") (pin "1") (pinfunction "1_1") (pintype "passive"))
      (node (ref "TP31") (pin "1") (pinfunction "G9_1") (pintype "passive"))
      (node (ref "U6") (pin "6") (pinfunction "VOD_6") (pintype "tri_state"))
      (node (ref "U7") (pin "1") (pinfunction "PB7/PB8_1") (pintype "bidirectional"))
    )
    (net (code "20") (name "/SWCLC") (class "Default")
      (node (ref "J1") (pin "3") (pinfunction "3_3") (pintype "passive"))
      (node (ref "R61") (pin "1") (pinfunction "1_1") (pintype "passive"))
      (node (ref "U7") (pin "19") (pinfunction "PA15/PA14-BOOT0_19") (pintype "bidirectional"))
    )
    (net (code "21") (name "/SWDIO") (class "Default")
      (node (ref "J1") (pin "2") (pinfunction "2_2") (pintype "passive"))
      (node (ref "U7") (pin "18") (pinfunction "PA13_18") (pintype "bidirectional"))
    )
    (net (code "22") (name "/TX") (class "Default")
      (node (ref "J1") (pin "4") (pinfunction "4_4") (pintype "passive"))
      (node (ref "R48") (pin "1") (pinfunction "1_1") (pintype "passive"))
      (node (ref "TP28") (pin "1") (pinfunction "G9_1") (pintype "passive"))
      (node (ref "U6") (pin "4") (pinfunction "VIB_4") (pintype "input"))
      (node (ref "U7") (pin "20") (pinfunction "PB3/PB4/PB5/PB6_20") (pintype "bidirectional"))
    )
    (net (code "23") (name "GND_2") (class "Default")
      (node (ref "C23") (pin "2") (pinfunction "2_2") (pintype "passive"))
      (node (ref "P1") (pin "2") (pinfunction "2_2") (pintype "passive"))
      (node (ref "R53") (pin "1") (pinfunction "1_1") (pintype "passive"))
      (node (ref "R56") (pin "1") (pinfunction "1_1") (pintype "passive"))
      (node (ref "TP33") (pin "1") (pinfunction "G9_1") (pintype "passive"))
      (node (ref "U2") (pin "3") (pinfunction "0V_3") (pintype "power_in"))
      (node (ref "U5") (pin "5") (pinfunction "GND_5") (pintype "power_in"))
      (node (ref "U6") (pin "15") (pinfunction "GND2_15") (pintype "power_in"))
      (node (ref "U6") (pin "9") (pinfunction "GND2_9") (pintype "power_in"))
      (node (ref "ZD2") (pin "1") (pinfunction "A_1") (pintype "passive"))
      (node (ref "ZD3") (pin "1") (pinfunction "A_1") (pintype "passive"))
    )
    (net (code "24") (name "GND_III") (class "Default")
      (node (ref "C1") (pin "2") (pinfunction "-_2") (pintype "passive"))
      (node (ref "C10") (pin "1") (pinfunction "1_1") (pintype "passive"))
      (node (ref "C11") (pin "2") (pinfunction "-_2") (pintype "passive"))
      (node (ref "C12") (pin "2") (pinfunction "2_2") (pintype "passive"))
      (node (ref "C13") (pin "2") (pinfunction "2_2") (pintype "passive"))
      (node (ref "C16") (pin "2") (pinfunction "2_2") (pintype "passive"))
      (node (ref "C17") (pin "1") (pinfunction "1_1") (pintype "passive"))
      (node (ref "C19") (pin "2") (pinfunction "2_2") (pintype "passive"))
      (node (ref "C2") (pin "2") (pinfunction "2_2") (pintype "passive"))
      (node (ref "C20") (pin "1") (pinfunction "1_1") (pintype "passive"))
      (node (ref "C21") (pin "2") (pinfunction "-_2") (pintype "passive"))
      (node (ref "C22") (pin "1") (pinfunction "1_1") (pintype "passive"))
      (node (ref "C24") (pin "2") (pinfunction "-_2") (pintype "passive"))
      (node (ref "C25") (pin "2") (pinfunction "2_2") (pintype "passive"))
      (node (ref "C26") (pin "2") (pinfunction "-_2") (pintype "passive"))
      (node (ref "C27") (pin "2") (pinfunction "-_2") (pintype "passive"))
      (node (ref "C28") (pin "2") (pinfunction "-_2") (pintype "passive"))
      (node (ref "C29") (pin "1") (pinfunction "1_1") (pintype "passive"))
      (node (ref "C3") (pin "2") (pinfunction "2_2") (pintype "passive"))
      (node (ref "C30") (pin "2") (pinfunction "-_2") (pintype "passive"))
      (node (ref "C31") (pin "2") (pinfunction "2_2") (pintype "passive"))
      (node (ref "C32") (pin "1") (pinfunction "1_1") (pintype "passive"))
      (node (ref "C33") (pin "2") (pinfunction "-_2") (pintype "passive"))
      (node (ref "C34") (pin "1") (pinfunction "1_1") (pintype "passive"))
      (node (ref "C35") (pin "1") (pinfunction "1_1") (pintype "passive"))
      (node (ref "C36") (pin "1") (pinfunction "1_1") (pintype "passive"))
      (node (ref "C37") (pin "1") (pinfunction "1_1") (pintype "passive"))
      (node (ref "C38") (pin "1") (pinfunction "1_1") (pintype "passive"))
      (node (ref "C41") (pin "1") (pinfunction "1_1") (pintype "passive"))
      (node (ref "C42") (pin "1") (pinfunction "1_1") (pintype "passive"))
      (node (ref "C43") (pin "1") (pinfunction "1_1") (pintype "passive"))
      (node (ref "C45") (pin "1") (pinfunction "1_1") (pintype "passive"))
      (node (ref "C48") (pin "1") (pinfunction "1_1") (pintype "passive"))
      (node (ref "C49") (pin "1") (pinfunction "1_1") (pintype "passive"))
      (node (ref "C50") (pin "1") (pinfunction "1_1") (pintype "passive"))
      (node (ref "C51") (pin "1") (pinfunction "1_1") (pintype "passive"))
      (node (ref "C52") (pin "1") (pinfunction "1_1") (pintype "passive"))
      (node (ref "C54") (pin "2") (pinfunction "-_2") (pintype "passive"))
      (node (ref "C55") (pin "1") (pinfunction "1_1") (pintype "passive"))
      (node (ref "C6") (pin "2") (pinfunction "2_2") (pintype "passive"))
      (node (ref "C7") (pin "1") (pinfunction "1_1") (pintype "passive"))
      (node (ref "C9") (pin "2") (pinfunction "2_2") (pintype "passive"))
      (node (ref "D2") (pin "2") (pinfunction "K_2") (pintype "passive"))
      (node (ref "D3") (pin "2") (pinfunction "K_2") (pintype "passive"))
      (node (ref "D4") (pin "2") (pinfunction "K_2") (pintype "passive"))
      (node (ref "DA2") (pin "3") (pinfunction "EMITTER_3") (pintype "passive"))
      (node (ref "DA4") (pin "3") (pinfunction "EMITTER_3") (pintype "passive"))
      (node (ref "DD1") (pin "12") (pinfunction "GND_12") (pintype "passive"))
      (node (ref "DD4") (pin "12") (pinfunction "GND_12") (pintype "passive"))
      (node (ref "J1") (pin "6") (pinfunction "6_6") (pintype "passive"))
      (node (ref "R1") (pin "1") (pinfunction "1_1") (pintype "passive"))
      (node (ref "R12") (pin "2") (pinfunction "2_2") (pintype "passive"))
      (node (ref "R18") (pin "1") (pinfunction "1_1") (pintype "passive"))
      (node (ref "R2") (pin "1") (pinfunction "1_1") (pintype "passive"))
      (node (ref "R22") (pin "1") (pinfunction "1_1") (pintype "passive"))
      (node (ref "R23") (pin "1") (pinfunction "1_1") (pintype "passive"))
      (node (ref "R24") (pin "1") (pinfunction "1_1") (pintype "passive"))
      (node (ref "R28") (pin "2") (pinfunction "2_2") (pintype "passive"))
      (node (ref "R3") (pin "1") (pinfunction "1_1") (pintype "passive"))
      (node (ref "R30") (pin "1") (pinfunction "1_1") (pintype "passive"))
      (node (ref "R33") (pin "2") (pinfunction "2_2") (pintype "passive"))
      (node (ref "R39") (pin "1") (pinfunction "1_1") (pintype "passive"))
      (node (ref "R55") (pin "1") (pinfunction "1_1") (pintype "passive"))
      (node (ref "R57") (pin "1") (pinfunction "1_1") (pintype "passive"))
      (node (ref "R61") (pin "2") (pinfunction "2_2") (pintype "passive"))
      (node (ref "R67") (pin "2") (pinfunction "2_2") (pintype "passive"))
      (node (ref "R68") (pin "1") (pinfunction "1_1") (pintype "passive"))
      (node (ref "R7") (pin "2") (pinfunction "2_2") (pintype "passive"))
      (node (ref "R76") (pin "2") (pinfunction "2_2") (pintype "passive"))
      (node (ref "R81") (pin "1") (pinfunction "1_1") (pintype "passive"))
      (node (ref "R82") (pin "1") (pinfunction "1_1") (pintype "passive"))
      (node (ref "R83") (pin "1") (pinfunction "1_1") (pintype "passive"))
      (node (ref "R9") (pin "1") (pinfunction "1_1") (pintype "passive"))
      (node (ref "TP3") (pin "1") (pinfunction "G9_1") (pintype "passive"))
      (node (ref "U1") (pin "3") (pinfunction "SD_3") (pintype "input"))
      (node (ref "U1") (pin "4") (pinfunction "GND_4") (pintype "power_in"))
      (node (ref "U10") (pin "2") (pinfunction "VSS_2") (pintype "power_in"))
      (node (ref "U2") (pin "1") (pinfunction "GND_1") (pintype "power_in"))
      (node (ref "U3") (pin "4") (pinfunction "GND_4") (pintype "power_in"))
      (node (ref "U4") (pin "1") (pinfunction "Ground_1") (pintype "power_in"))
      (node (ref "U6") (pin "2") (pinfunction "GND1_2") (pintype "power_in"))
      (node (ref "U6") (pin "8") (pinfunction "GND1_8") (pintype "power_in"))
      (node (ref "U7") (pin "5") (pinfunction "VSS/VSSA_5") (pintype "power_in"))
      (node (ref "U8") (pin "1") (pinfunction "Ground_1") (pintype "power_in"))
      (node (ref "U9") (pin "2") (pinfunction "VSS_2") (pintype "power_in"))
      (node (ref "VD11") (pin "1") (pinfunction "C_1") (pintype "passive"))
      (node (ref "VD12") (pin "2") (pinfunction "A_2") (pintype "passive"))
      (node (ref "VD13") (pin "2") (pinfunction "A_2") (pintype "passive"))
      (node (ref "VD5") (pin "1") (pinfunction "C_1") (pintype "passive"))
      (node (ref "VD6") (pin "2") (pinfunction "A_2") (pintype "passive"))
      (node (ref "VT1") (pin "3") (pinfunction "E_3") (pintype "passive"))
      (node (ref "VT2") (pin "3") (pinfunction "E_3") (pintype "passive"))
      (node (ref "X1") (pin "1") (pinfunction "1_1") (pintype "passive"))
      (node (ref "X2") (pin "2") (pinfunction "2_2") (pintype "passive"))
      (node (ref "X2") (pin "3") (pinfunction "3_3") (pintype "passive"))
      (node (ref "X3") (pin "2") (pinfunction "2_2") (pintype "passive"))
      (node (ref "X5") (pin "1") (pinfunction "1_1") (pintype "passive"))
      (node (ref "X6") (pin "2") (pinfunction "2_2") (pintype "passive"))
      (node (ref "X7") (pin "2") (pinfunction "2_2") (pintype "passive"))
      (node (ref "X7") (pin "3") (pinfunction "3_3") (pintype "passive"))
      (node (ref "X8") (pin "4") (pinfunction "4_4") (pintype "passive"))
      (node (ref "X9") (pin "2") (pinfunction "2_2") (pintype "passive"))
    )
    (net (code "25") (name "Net-(C26-+)") (class "Default")
      (node (ref "C26") (pin "1") (pinfunction "+_1") (pintype "passive"))
      (node (ref "JE1") (pin "1") (pinfunction "1_1") (pintype "passive"))
      (node (ref "L4") (pin "1") (pinfunction "1_1") (pintype "passive"))
      (node (ref "U1") (pin "8") (pinfunction "IN_8") (pintype "power_in"))
    )
    (net (code "26") (name "Net-(C27-+)") (class "Default")
      (node (ref "C27") (pin "1") (pinfunction "+_1") (pintype "passive"))
      (node (ref "C29") (pin "2") (pinfunction "2_2") (pintype "passive"))
      (node (ref "L4") (pin "2") (pinfunction "2_2") (pintype "passive"))
      (node (ref "TP25") (pin "1") (pinfunction "G9_1") (pintype "passive"))
      (node (ref "U4") (pin "3") (pinfunction "VIN_3") (pintype "power_in"))
    )
    (net (code "27") (name "Net-(C28-+)") (class "Default")
      (node (ref "C28") (pin "1") (pinfunction "+_1") (pintype "passive"))
      (node (ref "JE1") (pin "2") (pinfunction "2_2") (pintype "passive"))
      (node (ref "L3") (pin "2") (pinfunction "2_2") (pintype "passive"))
      (node (ref "R52") (pin "1") (pinfunction "1_1") (pintype "passive"))
    )
    (net (code "28") (name "Net-(C41-Pad2)") (class "Default")
      (node (ref "C41") (pin "2") (pinfunction "2_2") (pintype "passive"))
      (node (ref "R62") (pin "1") (pinfunction "1_1") (pintype "passive"))
      (node (ref "R63") (pin "2") (pinfunction "2_2") (pintype "passive"))
    )
    (net (code "29") (name "Net-(C48-Pad2)") (class "Default")
      (node (ref "C48") (pin "2") (pinfunction "2_2") (pintype "passive"))
      (node (ref "R72") (pin "1") (pinfunction "1_1") (pintype "passive"))
      (node (ref "R73") (pin "2") (pinfunction "2_2") (pintype "passive"))
    )
    (net (code "30") (name "Net-(D2-A)") (class "Default")
      (node (ref "D2") (pin "1") (pinfunction "A_1") (pintype "passive"))
      (node (ref "R54") (pin "1") (pinfunction "1_1") (pintype "passive"))
    )
    (net (code "31") (name "Net-(D3-A)") (class "Default")
      (node (ref "D3") (pin "1") (pinfunction "A_1") (pintype "passive"))
      (node (ref "R59") (pin "2") (pinfunction "2_2") (pintype "passive"))
    )
    (net (code "32") (name "Net-(D4-A)") (class "Default")
      (node (ref "D4") (pin "1") (pinfunction "A_1") (pintype "passive"))
      (node (ref "R65") (pin "2") (pinfunction "2_2") (pintype "passive"))
    )
    (net (code "33") (name "Net-(DA1-CATHODE)") (class "Default")
      (node (ref "DA1") (pin "2") (pinfunction "CATHODE_2") (pintype "passive"))
      (node (ref "R1") (pin "2") (pinfunction "2_2") (pintype "passive"))
    )
    (net (code "34") (name "Net-(DA1-COLLECTOR)") (class "Default")
      (node (ref "C2") (pin "1") (pinfunction "1_1") (pintype "passive"))
      (node (ref "C6") (pin "1") (pinfunction "1_1") (pintype "passive"))
      (node (ref "DA1") (pin "4") (pinfunction "COLLECTOR_4") (pintype "passive"))
      (node (ref "DD1") (pin "1") (pinfunction "INV_IN_1") (pintype "passive"))
      (node (ref "R2") (pin "2") (pinfunction "2_2") (pintype "passive"))
      (node (ref "R20") (pin "2") (pinfunction "2_2") (pintype "passive"))
      (node (ref "TP1") (pin "1") (pinfunction "G9_1") (pintype "passive"))
    )
    (net (code "35") (name "Net-(DA1-EMITTER)") (class "Default")
      (node (ref "DA1") (pin "3") (pinfunction "EMITTER_3") (pintype "passive"))
      (node (ref "R3") (pin "2") (pinfunction "2_2") (pintype "passive"))
    )
    (net (code "36") (name "Net-(DA2-ANODE)") (class "Default")
      (node (ref "DA2") (pin "1") (pinfunction "ANODE_1") (pintype "passive"))
      (node (ref "R4") (pin "1") (pinfunction "1_1") (pintype "passive"))
    )
    (net (code "37") (name "Net-(DA2-CATHODE)") (class "Default")
      (node (ref "DA2") (pin "2") (pinfunction "CATHODE_2") (pintype "passive"))
      (node (ref "TP2") (pin "1") (pinfunction "G9_1") (pintype "passive"))
      (node (ref "VT1") (pin "2") (pinfunction "C_2") (pintype "passive"))
    )
    (net (code "38") (name "Net-(DA3-CATHODE)") (class "Default")
      (node (ref "DA3") (pin "2") (pinfunction "CATHODE_2") (pintype "passive"))
      (node (ref "R22") (pin "2") (pinfunction "2_2") (pintype "passive"))
    )
    (net (code "39") (name "Net-(DA3-COLLECTOR)") (class "Default")
      (node (ref "C12") (pin "1") (pinfunction "1_1") (pintype "passive"))
      (node (ref "C16") (pin "1") (pinfunction "1_1") (pintype "passive"))
      (node (ref "DA3") (pin "4") (pinfunction "COLLECTOR_4") (pintype "passive"))
      (node (ref "DD4") (pin "1") (pinfunction "INV_IN_1") (pintype "passive"))
      (node (ref "R23") (pin "2") (pinfunction "2_2") (pintype "passive"))
      (node (ref "R41") (pin "2") (pinfunction "2_2") (pintype "passive"))
      (node (ref "TP12") (pin "1") (pinfunction "G9_1") (pintype "passive"))
    )
    (net (code "40") (name "Net-(DA3-EMITTER)") (class "Default")
      (node (ref "DA3") (pin "3") (pinfunction "EMITTER_3") (pintype "passive"))
      (node (ref "R24") (pin "2") (pinfunction "2_2") (pintype "passive"))
    )
    (net (code "41") (name "Net-(DA4-ANODE)") (class "Default")
      (node (ref "DA4") (pin "1") (pinfunction "ANODE_1") (pintype "passive"))
      (node (ref "R25") (pin "1") (pinfunction "1_1") (pintype "passive"))
    )
    (net (code "42") (name "Net-(DA4-CATHODE)") (class "Default")
      (node (ref "DA4") (pin "2") (pinfunction "CATHODE_2") (pintype "passive"))
      (node (ref "TP13") (pin "1") (pinfunction "G9_1") (pintype "passive"))
      (node (ref "VT2") (pin "2") (pinfunction "C_2") (pintype "passive"))
    )
    (net (code "43") (name "Net-(DD1-COMPENSATION)") (class "Default")
      (node (ref "DD1") (pin "9") (pinfunction "COMPENSATION_9") (pintype "passive"))
      (node (ref "R20") (pin "1") (pinfunction "1_1") (pintype "passive"))
    )
    (net (code "44") (name "Net-(DD1-CT)") (class "Default")
      (node (ref "DD1") (pin "5") (pinfunction "CT_5") (pintype "passive"))
      (node (ref "R14") (pin "1") (pinfunction "1_1") (pintype "passive"))
    )
    (net (code "45") (name "Net-(DD1-DISCHARGE)") (class "Default")
      (node (ref "DD1") (pin "7") (pinfunction "DISCHARGE_7") (pintype "passive"))
      (node (ref "R17") (pin "1") (pinfunction "1_1") (pintype "passive"))
    )
    (net (code "46") (name "Net-(DD1-NON_INV_IN)") (class "Default")
      (node (ref "DD1") (pin "2") (pinfunction "NON_INV_IN_2") (pintype "passive"))
      (node (ref "R7") (pin "1") (pinfunction "1_1") (pintype "passive"))
      (node (ref "R8") (pin "2") (pinfunction "2_2") (pintype "passive"))
      (node (ref "TP8") (pin "1") (pinfunction "G9_1") (pintype "passive"))
    )
    (net (code "47") (name "Net-(DD1-SHUT_DOWN)") (class "Default")
      (node (ref "C10") (pin "2") (pinfunction "2_2") (pintype "passive"))
      (node (ref "DD1") (pin "10") (pinfunction "SHUT_DOWN_10") (pintype "passive"))
      (node (ref "R15") (pin "1") (pinfunction "1_1") (pintype "passive"))
      (node (ref "R18") (pin "2") (pinfunction "2_2") (pintype "passive"))
    )
    (net (code "48") (name "Net-(DD1-SOFT_START)") (class "Default")
      (node (ref "C9") (pin "1") (pinfunction "1_1") (pintype "passive"))
      (node (ref "DD1") (pin "8") (pinfunction "SOFT_START_8") (pintype "passive"))
    )
    (net (code "49") (name "Net-(DD1-SYNC)") (class "Default")
      (node (ref "DD1") (pin "3") (pinfunction "SYNC_3") (pintype "passive"))
      (node (ref "R12") (pin "1") (pinfunction "1_1") (pintype "passive"))
    )
    (net (code "50") (name "Net-(DD1-V_REF)") (class "Default")
      (node (ref "C3") (pin "1") (pinfunction "1_1") (pintype "passive"))
      (node (ref "DD1") (pin "16") (pinfunction "V_REF_16") (pintype "passive"))
      (node (ref "R2") (pin "3") (pinfunction "3_3") (pintype "passive"))
      (node (ref "R8") (pin "1") (pinfunction "1_1") (pintype "passive"))
    )
    (net (code "51") (name "Net-(DD2-VIN-)") (class "Default")
      (node (ref "DD2") (pin "4") (pinfunction "VIN-_4") (pintype "passive"))
      (node (ref "R11") (pin "2") (pinfunction "2_2") (pintype "passive"))
      (node (ref "R13") (pin "1") (pinfunction "1_1") (pintype "passive"))
    )
    (net (code "52") (name "Net-(DD2-VOUT)") (class "Default")
      (node (ref "DD2") (pin "1") (pinfunction "VOUT_1") (pintype "passive"))
      (node (ref "R11") (pin "1") (pinfunction "1_1") (pintype "passive"))
      (node (ref "R6") (pin "1") (pinfunction "1_1") (pintype "passive"))
    )
    (net (code "53") (name "Net-(DD2-VSS)") (class "Default")
      (node (ref "C4") (pin "1") (pinfunction "1_1") (pintype "passive"))
      (node (ref "C5") (pin "1") (pinfunction "1_1") (pintype "passive"))
      (node (ref "C8") (pin "2") (pinfunction "2_2") (pintype "passive"))
      (node (ref "DD2") (pin "2") (pinfunction "VSS_2") (pintype "passive"))
      (node (ref "DD3") (pin "2") (pinfunction "VSS_2") (pintype "passive"))
      (node (ref "R13") (pin "2") (pinfunction "2_2") (pintype "passive"))
      (node (ref "R21") (pin "2") (pinfunction "2_2") (pintype "passive"))
      (node (ref "VD3") (pin "2") (pinfunction "A_2") (pintype "passive"))
      (node (ref "VD4") (pin "1") (pinfunction "C_1") (pintype "passive"))
    )
    (net (code "54") (name "Net-(DD3-VIN+)") (class "Default")
      (node (ref "C8") (pin "1") (pinfunction "1_1") (pintype "passive"))
      (node (ref "DD3") (pin "3") (pinfunction "VIN+_3") (pintype "passive"))
      (node (ref "R10") (pin "2") (pinfunction "2_2") (pintype "passive"))
      (node (ref "TP9") (pin "1") (pinfunction "G9_1") (pintype "passive"))
      (node (ref "VD1") (pin "2") (pinfunction "A_2") (pintype "passive"))
      (node (ref "VD2") (pin "2") (pinfunction "A_2") (pintype "passive"))
    )
    (net (code "55") (name "Net-(DD3-VIN-)") (class "Default")
      (node (ref "DD3") (pin "4") (pinfunction "VIN-_4") (pintype "passive"))
      (node (ref "R19") (pin "2") (pinfunction "2_2") (pintype "passive"))
      (node (ref "R21") (pin "1") (pinfunction "1_1") (pintype "passive"))
    )
    (net (code "56") (name "Net-(DD3-VOUT)") (class "Default")
      (node (ref "DD3") (pin "1") (pinfunction "VOUT_1") (pintype "passive"))
      (node (ref "R14") (pin "2") (pinfunction "2_2") (pintype "passive"))
      (node (ref "R19") (pin "1") (pinfunction "1_1") (pintype "passive"))
      (node (ref "TP6") (pin "1") (pinfunction "G9_1") (pintype "passive"))
    )
    (net (code "57") (name "Net-(DD4-COMPENSATION)") (class "Default")
      (node (ref "DD4") (pin "9") (pinfunction "COMPENSATION_9") (pintype "passive"))
      (node (ref "R41") (pin "1") (pinfunction "1_1") (pintype "passive"))
    )
    (net (code "58") (name "Net-(DD4-CT)") (class "Default")
      (node (ref "DD4") (pin "5") (pinfunction "CT_5") (pintype "passive"))
      (node (ref "R35") (pin "1") (pinfunction "1_1") (pintype "passive"))
    )
    (net (code "59") (name "Net-(DD4-DISCHARGE)") (class "Default")
      (node (ref "DD4") (pin "7") (pinfunction "DISCHARGE_7") (pintype "passive"))
      (node (ref "R38") (pin "1") (pinfunction "1_1") (pintype "passive"))
    )
    (net (code "60") (name "Net-(DD4-NON_INV_IN)") (class "Default")
      (node (ref "DD4") (pin "2") (pinfunction "NON_INV_IN_2") (pintype "passive"))
      (node (ref "R28") (pin "1") (pinfunction "1_1") (pintype "passive"))
      (node (ref "R29") (pin "2") (pinfunction "2_2") (pintype "passive"))
      (node (ref "TP19") (pin "1") (pinfunction "G9_1") (pintype "passive"))
    )
    (net (code "61") (name "Net-(DD4-SHUT_DOWN)") (class "Default")
      (node (ref "C20") (pin "2") (pinfunction "2_2") (pintype "passive"))
      (node (ref "DD4") (pin "10") (pinfunction "SHUT_DOWN_10") (pintype "passive"))
      (node (ref "R36") (pin "1") (pinfunction "1_1") (pintype "passive"))
      (node (ref "R39") (pin "2") (pinfunction "2_2") (pintype "passive"))
    )
    (net (code "62") (name "Net-(DD4-SOFT_START)") (class "Default")
      (node (ref "C19") (pin "1") (pinfunction "1_1") (pintype "passive"))
      (node (ref "DD4") (pin "8") (pinfunction "SOFT_START_8") (pintype "passive"))
    )
    (net (code "63") (name "Net-(DD4-SYNC)") (class "Default")
      (node (ref "DD4") (pin "3") (pinfunction "SYNC_3") (pintype "passive"))
      (node (ref "R33") (pin "1") (pinfunction "1_1") (pintype "passive"))
    )
    (net (code "64") (name "Net-(DD4-V_REF)") (class "Default")
      (node (ref "C13") (pin "1") (pinfunction "1_1") (pintype "passive"))
      (node (ref "DD4") (pin "16") (pinfunction "V_REF_16") (pintype "passive"))
      (node (ref "R23") (pin "3") (pinfunction "3_3") (pintype "passive"))
      (node (ref "R29") (pin "1") (pinfunction "1_1") (pintype "passive"))
    )
    (net (code "65") (name "Net-(DD5-VIN-)") (class "Default")
      (node (ref "DD5") (pin "4") (pinfunction "VIN-_4") (pintype "passive"))
      (node (ref "R32") (pin "2") (pinfunction "2_2") (pintype "passive"))
      (node (ref "R34") (pin "1") (pinfunction "1_1") (pintype "passive"))
    )
    (net (code "66") (name "Net-(DD5-VOUT)") (class "Default")
      (node (ref "DD5") (pin "1") (pinfunction "VOUT_1") (pintype "passive"))
      (node (ref "R27") (pin "1") (pinfunction "1_1") (pintype "passive"))
      (node (ref "R32") (pin "1") (pinfunction "1_1") (pintype "passive"))
    )
    (net (code "67") (name "Net-(DD5-VSS)") (class "Default")
      (node (ref "C14") (pin "1") (pinfunction "1_1") (pintype "passive"))
      (node (ref "C15") (pin "1") (pinfunction "1_1") (pintype "passive"))
      (node (ref "C18") (pin "2") (pinfunction "2_2") (pintype "passive"))
      (node (ref "DD5") (pin "2") (pinfunction "VSS_2") (pintype "passive"))
      (node (ref "DD6") (pin "2") (pinfunction "VSS_2") (pintype "passive"))
      (node (ref "R34") (pin "2") (pinfunction "2_2") (pintype "passive"))
      (node (ref "R42") (pin "2") (pinfunction "2_2") (pintype "passive"))
      (node (ref "VD10") (pin "1") (pinfunction "C_1") (pintype "passive"))
      (node (ref "VD9") (pin "2") (pinfunction "A_2") (pintype "passive"))
    )
    (net (code "68") (name "Net-(DD6-VIN+)") (class "Default")
      (node (ref "C18") (pin "1") (pinfunction "1_1") (pintype "passive"))
      (node (ref "DD6") (pin "3") (pinfunction "VIN+_3") (pintype "passive"))
      (node (ref "R31") (pin "2") (pinfunction "2_2") (pintype "passive"))
      (node (ref "TP20") (pin "1") (pinfunction "G9_1") (pintype "passive"))
      (node (ref "VD7") (pin "2") (pinfunction "A_2") (pintype "passive"))
      (node (ref "VD8") (pin "2") (pinfunction "A_2") (pintype "passive"))
    )
    (net (code "69") (name "Net-(DD6-VIN-)") (class "Default")
      (node (ref "DD6") (pin "4") (pinfunction "VIN-_4") (pintype "passive"))
      (node (ref "R40") (pin "2") (pinfunction "2_2") (pintype "passive"))
      (node (ref "R42") (pin "1") (pinfunction "1_1") (pintype "passive"))
    )
    (net (code "70") (name "Net-(DD6-VOUT)") (class "Default")
      (node (ref "DD6") (pin "1") (pinfunction "VOUT_1") (pintype "passive"))
      (node (ref "R35") (pin "2") (pinfunction "2_2") (pintype "passive"))
      (node (ref "R40") (pin "1") (pinfunction "1_1") (pintype "passive"))
      (node (ref "TP17") (pin "1") (pinfunction "G9_1") (pintype "passive"))
    )
    (net (code "71") (name "Net-(L1-Pad1)") (class "Default")
      (node (ref "L1") (pin "1") (pinfunction "1_1") (pintype "passive"))
      (node (ref "R4") (pin "2") (pinfunction "2_2") (pintype "passive"))
    )
    (net (code "72") (name "Net-(L2-Pad1)") (class "Default")
      (node (ref "L2") (pin "1") (pinfunction "1_1") (pintype "passive"))
      (node (ref "R25") (pin "2") (pinfunction "2_2") (pintype "passive"))
    )
    (net (code "73") (name "Net-(TP5-G9)") (class "Default")
      (node (ref "R10") (pin "1") (pinfunction "1_1") (pintype "passive"))
      (node (ref "R6") (pin "2") (pinfunction "2_2") (pintype "passive"))
      (node (ref "R6") (pin "3") (pinfunction "3_3") (pintype "passive"))
      (node (ref "TP5") (pin "1") (pinfunction "G9_1") (pintype "passive"))
      (node (ref "VD1") (pin "1") (pinfunction "C_1") (pintype "passive"))
    )
    (net (code "74") (name "Net-(TP11-G9)") (class "Default")
      (node (ref "R17") (pin "2") (pinfunction "2_2") (pintype "passive"))
      (node (ref "TP11") (pin "1") (pinfunction "G9_1") (pintype "passive"))
      (node (ref "VD2") (pin "1") (pinfunction "C_1") (pintype "passive"))
    )
    (net (code "75") (name "Net-(TP16-G9)") (class "Default")
      (node (ref "R27") (pin "2") (pinfunction "2_2") (pintype "passive"))
      (node (ref "R27") (pin "3") (pinfunction "3_3") (pintype "passive"))
      (node (ref "R31") (pin "1") (pinfunction "1_1") (pintype "passive"))
      (node (ref "TP16") (pin "1") (pinfunction "G9_1") (pintype "passive"))
      (node (ref "VD7") (pin "1") (pinfunction "C_1") (pintype "passive"))
    )
    (net (code "76") (name "Net-(TP22-G9)") (class "Default")
      (node (ref "R38") (pin "2") (pinfunction "2_2") (pintype "passive"))
      (node (ref "TP22") (pin "1") (pinfunction "G9_1") (pintype "passive"))
      (node (ref "VD8") (pin "1") (pinfunction "C_1") (pintype "passive"))
    )
    (net (code "77") (name "Net-(TP24-G9)") (class "Default")
      (node (ref "L3") (pin "1") (pinfunction "1_1") (pintype "passive"))
      (node (ref "TP24") (pin "1") (pinfunction "G9_1") (pintype "passive"))
      (node (ref "U3") (pin "2") (pinfunction "SWE_2") (pintype "open_emitter"))
      (node (ref "VD13") (pin "1") (pinfunction "C_1") (pintype "passive"))
    )
    (net (code "78") (name "Net-(TP26-G9)") (class "Default")
      (node (ref "R46") (pin "1") (pinfunction "1_1") (pintype "passive"))
      (node (ref "R50") (pin "1") (pinfunction "1_1") (pintype "passive"))
      (node (ref "TP26") (pin "1") (pinfunction "G9_1") (pintype "passive"))
      (node (ref "U5") (pin "4") (pinfunction "DI_4") (pintype "input"))
    )
    (net (code "79") (name "Net-(TP30-G9)") (class "Default")
      (node (ref "R53") (pin "2") (pinfunction "2_2") (pintype "passive"))
      (node (ref "TP30") (pin "1") (pinfunction "G9_1") (pintype "passive"))
      (node (ref "U5") (pin "2") (pinfunction "~{RE}_2") (pintype "input"))
      (node (ref "U5") (pin "3") (pinfunction "DE_3") (pintype "input"))
      (node (ref "U6") (pin "12") (pinfunction "VOC_12") (pintype "tri_state"))
    )
    (net (code "80") (name "Net-(TP32-G9)") (class "Default")
      (node (ref "R47") (pin "1") (pinfunction "1_1") (pintype "passive"))
      (node (ref "R51") (pin "1") (pinfunction "1_1") (pintype "passive"))
      (node (ref "TP32") (pin "1") (pinfunction "G9_1") (pintype "passive"))
      (node (ref "U5") (pin "1") (pinfunction "RO_1") (pintype "output"))
    )
    (net (code "81") (name "Net-(TP37-G9)") (class "Default")
      (node (ref "C39") (pin "2") (pinfunction "2_2") (pintype "passive"))
      (node (ref "C43") (pin "2") (pinfunction "2_2") (pintype "passive"))
      (node (ref "R60") (pin "2") (pinfunction "2_2") (pintype "passive"))
      (node (ref "R68") (pin "2") (pinfunction "2_2") (pintype "passive"))
      (node (ref "TP37") (pin "1") (pinfunction "G9_1") (pintype "passive"))
      (node (ref "U9") (pin "3") (pinfunction "VIN+_3") (pintype "input"))
    )
    (net (code "82") (name "Net-(TP38-G9)") (class "Default")
      (node (ref "C42") (pin "2") (pinfunction "2_2") (pintype "passive"))
      (node (ref "R63") (pin "1") (pinfunction "1_1") (pintype "passive"))
      (node (ref "R64") (pin "2") (pinfunction "2_2") (pintype "passive"))
      (node (ref "R67") (pin "1") (pinfunction "1_1") (pintype "passive"))
      (node (ref "TP38") (pin "1") (pinfunction "G9_1") (pintype "passive"))
    )
    (net (code "83") (name "Net-(TP39-G9)") (class "Default")
      (node (ref "C44") (pin "2") (pinfunction "2_2") (pintype "passive"))
      (node (ref "R62") (pin "2") (pinfunction "2_2") (pintype "passive"))
      (node (ref "R69") (pin "2") (pinfunction "2_2") (pintype "passive"))
      (node (ref "TP39") (pin "1") (pinfunction "G9_1") (pintype "passive"))
      (node (ref "U9") (pin "1") (pinfunction "VOUT_1") (pintype "output"))
    )
    (net (code "84") (name "Net-(TP42-G9)") (class "Default")
      (node (ref "C39") (pin "1") (pinfunction "1_1") (pintype "passive"))
      (node (ref "C44") (pin "1") (pinfunction "1_1") (pintype "passive"))
      (node (ref "R66") (pin "2") (pinfunction "2_2") (pintype "passive"))
      (node (ref "R69") (pin "1") (pinfunction "1_1") (pintype "passive"))
      (node (ref "TP42") (pin "1") (pinfunction "G9_1") (pintype "passive"))
      (node (ref "U9") (pin "4") (pinfunction "VIN-_4") (pintype "input"))
    )
    (net (code "85") (name "Net-(TP45-G9)") (class "Default")
      (node (ref "C46") (pin "2") (pinfunction "2_2") (pintype "passive"))
      (node (ref "C51") (pin "2") (pinfunction "2_2") (pintype "passive"))
      (node (ref "R71") (pin "2") (pinfunction "2_2") (pintype "passive"))
      (node (ref "R81") (pin "2") (pinfunction "2_2") (pintype "passive"))
      (node (ref "TP45") (pin "1") (pinfunction "G9_1") (pintype "passive"))
      (node (ref "U10") (pin "3") (pinfunction "VIN+_3") (pintype "input"))
    )
    (net (code "86") (name "Net-(TP47-G9)") (class "Default")
      (node (ref "C49") (pin "2") (pinfunction "2_2") (pintype "passive"))
      (node (ref "R73") (pin "1") (pinfunction "1_1") (pintype "passive"))
      (node (ref "R74") (pin "2") (pinfunction "2_2") (pintype "passive"))
      (node (ref "R76") (pin "1") (pinfunction "1_1") (pintype "passive"))
      (node (ref "TP47") (pin "1") (pinfunction "G9_1") (pintype "passive"))
    )
    (net (code "87") (name "Net-(TP48-G9)") (class "Default")
      (node (ref "C53") (pin "2") (pinfunction "2_2") (pintype "passive"))
      (node (ref "R72") (pin "2") (pinfunction "2_2") (pintype "passive"))
      (node (ref "R84") (pin "2") (pinfunction "2_2") (pintype "passive"))
      (node (ref "TP48") (pin "1") (pinfunction "G9_1") (pintype "passive"))
      (node (ref "U10") (pin "1") (pinfunction "VOUT_1") (pintype "output"))
    )
    (net (code "88") (name "Net-(TP51-G9)") (class "Default")
      (node (ref "C46") (pin "1") (pinfunction "1_1") (pintype "passive"))
      (node (ref "C53") (pin "1") (pinfunction "1_1") (pintype "passive"))
      (node (ref "R75") (pin "2") (pinfunction "2_2") (pintype "passive"))
      (node (ref "R84") (pin "1") (pinfunction "1_1") (pintype "passive"))
      (node (ref "TP51") (pin "1") (pinfunction "G9_1") (pintype "passive"))
      (node (ref "U10") (pin "4") (pinfunction "VIN-_4") (pintype "input"))
    )
    (net (code "89") (name "Net-(U1-FB)") (class "Default")
      (node (ref "U1") (pin "6") (pinfunction "VTAP_6") (pintype "passive"))
      (node (ref "U1") (pin "7") (pinfunction "FB_7") (pintype "input"))
    )
    (net (code "90") (name "Net-(U1-~{ERR})") (class "Default")
      (node (ref "R43") (pin "2") (pinfunction "2_2") (pintype "passive"))
      (node (ref "U1") (pin "5") (pinfunction "~{ERR}_5") (pintype "open_collector"))
    )
    (net (code "91") (name "Net-(U3-CII)") (class "Default")
      (node (ref "R52") (pin "2") (pinfunction "2_2") (pintype "passive"))
      (node (ref "R57") (pin "2") (pinfunction "2_2") (pintype "passive"))
      (node (ref "U3") (pin "5") (pinfunction "CII_5") (pintype "input"))
    )
    (net (code "92") (name "Net-(U3-DRC)") (class "Default")
      (node (ref "R49") (pin "2") (pinfunction "2_2") (pintype "passive"))
      (node (ref "U3") (pin "1") (pinfunction "SWC_1") (pintype "open_collector"))
      (node (ref "U3") (pin "7") (pinfunction "IPK_7") (pintype "passive"))
      (node (ref "U3") (pin "8") (pinfunction "DRC_8") (pintype "open_collector"))
    )
    (net (code "93") (name "Net-(U3-TC)") (class "Default")
      (node (ref "C25") (pin "1") (pinfunction "1_1") (pintype "passive"))
      (node (ref "U3") (pin "3") (pinfunction "TC_3") (pintype "passive"))
    )
    (net (code "94") (name "Net-(U5-A)") (class "Default")
      (node (ref "P1") (pin "3") (pinfunction "3_3") (pintype "passive"))
      (node (ref "R44") (pin "1") (pinfunction "1_1") (pintype "passive"))
      (node (ref "U5") (pin "6") (pinfunction "A_6") (pintype "bidirectional"))
      (node (ref "ZD1") (pin "2") (pinfunction "A_2") (pintype "passive"))
      (node (ref "ZD2") (pin "2") (pinfunction "A_2") (pintype "passive"))
    )
    (net (code "95") (name "Net-(U5-B)") (class "Default")
      (node (ref "P1") (pin "1") (pinfunction "1_1") (pintype "passive"))
      (node (ref "R56") (pin "2") (pinfunction "2_2") (pintype "passive"))
      (node (ref "U5") (pin "7") (pinfunction "B_7") (pintype "bidirectional"))
      (node (ref "ZD1") (pin "1") (pinfunction "A_1") (pintype "passive"))
      (node (ref "ZD3") (pin "2") (pinfunction "A_2") (pintype "passive"))
    )
    (net (code "96") (name "Net-(U6-VID)") (class "Default")
      (node (ref "R51") (pin "2") (pinfunction "2_2") (pintype "passive"))
      (node (ref "U6") (pin "11") (pinfunction "VID_11") (pintype "input"))
    )
    (net (code "97") (name "Net-(U6-VOB)") (class "Default")
      (node (ref "R50") (pin "2") (pinfunction "2_2") (pintype "passive"))
      (node (ref "U6") (pin "13") (pinfunction "VOB_13") (pintype "tri_state"))
    )
    (net (code "98") (name "Net-(U7-PA12[PA10])") (class "Default")
      (node (ref "R59") (pin "1") (pinfunction "1_1") (pintype "passive"))
      (node (ref "U7") (pin "17") (pinfunction "PA12[PA10]_17") (pintype "bidirectional"))
    )
    (net (code "99") (name "Net-(U7-PC15-OSC32_OUT)") (class "Default")
      (node (ref "R65") (pin "1") (pinfunction "1_1") (pintype "passive"))
      (node (ref "U7") (pin "3") (pinfunction "PC15-OSC32_OUT_3") (pintype "bidirectional"))
    )
    (net (code "100") (name "Net-(U7-~{RST})") (class "Default")
      (node (ref "C34") (pin "2") (pinfunction "2_2") (pintype "passive"))
      (node (ref "R58") (pin "2") (pinfunction "2_2") (pintype "passive"))
      (node (ref "U7") (pin "6") (pinfunction "~{RST}_6") (pintype "input"))
    )
    (net (code "101") (name "Net-(VD3-C)") (class "Default")
      (node (ref "VD3") (pin "1") (pinfunction "C_1") (pintype "passive"))
      (node (ref "VD5") (pin "2") (pinfunction "A_2") (pintype "passive"))
    )
    (net (code "102") (name "Net-(VD4-A)") (class "Default")
      (node (ref "VD4") (pin "2") (pinfunction "A_2") (pintype "passive"))
      (node (ref "VD6") (pin "1") (pinfunction "C_1") (pintype "passive"))
    )
    (net (code "103") (name "Net-(VD10-A)") (class "Default")
      (node (ref "VD10") (pin "2") (pinfunction "A_2") (pintype "passive"))
      (node (ref "VD12") (pin "1") (pinfunction "C_1") (pintype "passive"))
    )
    (net (code "104") (name "Net-(VD11-A)") (class "Default")
      (node (ref "VD11") (pin "2") (pinfunction "A_2") (pintype "passive"))
      (node (ref "VD9") (pin "1") (pinfunction "C_1") (pintype "passive"))
    )
    (net (code "105") (name "Net-(VT1-B)") (class "Default")
      (node (ref "R5") (pin "2") (pinfunction "2_2") (pintype "passive"))
      (node (ref "VT1") (pin "1") (pinfunction "B_1") (pintype "passive"))
    )
    (net (code "106") (name "Net-(VT2-B)") (class "Default")
      (node (ref "R26") (pin "2") (pinfunction "2_2") (pintype "passive"))
      (node (ref "VT2") (pin "1") (pinfunction "B_1") (pintype "passive"))
    )
    (net (code "107") (name "OUT_A1") (class "Default")
      (node (ref "DD1") (pin "11") (pinfunction "OUT_A_11") (pintype "passive"))
      (node (ref "TP10") (pin "1") (pinfunction "G9_1") (pintype "passive"))
      (node (ref "X2") (pin "4") (pinfunction "4_4") (pintype "passive"))
    )
    (net (code "108") (name "OUT_A2") (class "Default")
      (node (ref "DD4") (pin "11") (pinfunction "OUT_A_11") (pintype "passive"))
      (node (ref "TP21") (pin "1") (pinfunction "G9_1") (pintype "passive"))
      (node (ref "X7") (pin "4") (pinfunction "4_4") (pintype "passive"))
    )
    (net (code "109") (name "OUT_B1") (class "Default")
      (node (ref "DD1") (pin "14") (pinfunction "OUT_B_14") (pintype "passive"))
      (node (ref "TP7") (pin "1") (pinfunction "G9_1") (pintype "passive"))
      (node (ref "X2") (pin "1") (pinfunction "1_1") (pintype "passive"))
    )
    (net (code "110") (name "OUT_B2") (class "Default")
      (node (ref "DD4") (pin "14") (pinfunction "OUT_B_14") (pintype "passive"))
      (node (ref "TP18") (pin "1") (pinfunction "G9_1") (pintype "passive"))
      (node (ref "X7") (pin "1") (pinfunction "1_1") (pintype "passive"))
    )
    (net (code "111") (name "PWM_1") (class "Default")
      (node (ref "DD2") (pin "3") (pinfunction "VIN+_3") (pintype "passive"))
      (node (ref "R9") (pin "2") (pinfunction "2_2") (pintype "passive"))
      (node (ref "TP4") (pin "1") (pinfunction "G9_1") (pintype "passive"))
      (node (ref "U7") (pin "15") (pinfunction "PB0/PB1/PB2/PA8_15") (pintype "bidirectional"))
    )
    (net (code "112") (name "PWM_2") (class "Default")
      (node (ref "DD5") (pin "3") (pinfunction "VIN+_3") (pintype "passive"))
      (node (ref "R30") (pin "2") (pinfunction "2_2") (pintype "passive"))
      (node (ref "TP15") (pin "1") (pinfunction "G9_1") (pintype "passive"))
      (node (ref "U7") (pin "13") (pinfunction "PA6_13") (pintype "bidirectional"))
    )
    (net (code "113") (name "PWM_SET_1") (class "Default")
      (node (ref "DA1") (pin "1") (pinfunction "ANODE_1") (pintype "passive"))
      (node (ref "U7") (pin "16") (pinfunction "PA11[PA9]_16") (pintype "bidirectional"))
    )
    (net (code "114") (name "PWM_SET_2") (class "Default")
      (node (ref "DA3") (pin "1") (pinfunction "ANODE_1") (pintype "passive"))
      (node (ref "U7") (pin "14") (pinfunction "PA7_14") (pintype "bidirectional"))
    )
    (net (code "115") (name "SD_1") (class "Default")
      (node (ref "R5") (pin "1") (pinfunction "1_1") (pintype "passive"))
      (node (ref "U7") (pin "11") (pinfunction "PA4_11") (pintype "bidirectional"))
    )
    (net (code "116") (name "SD_2") (class "Default")
      (node (ref "R26") (pin "1") (pinfunction "1_1") (pintype "passive"))
      (node (ref "U7") (pin "12") (pinfunction "PA5_12") (pintype "bidirectional"))
    )
    (net (code "117") (name "SD_G_1") (class "Default")
      (node (ref "DA2") (pin "4") (pinfunction "COLLECTOR_4") (pintype "passive"))
      (node (ref "R15") (pin "2") (pinfunction "2_2") (pintype "passive"))
      (node (ref "TP52") (pin "1") (pinfunction "G9_1") (pintype "passive"))
      (node (ref "X4") (pin "1") (pinfunction "1_1") (pintype "passive"))
    )
    (net (code "118") (name "SD_G_2") (class "Default")
      (node (ref "DA4") (pin "4") (pinfunction "COLLECTOR_4") (pintype "passive"))
      (node (ref "R36") (pin "2") (pinfunction "2_2") (pintype "passive"))
      (node (ref "TP53") (pin "1") (pinfunction "G9_1") (pintype "passive"))
      (node (ref "X8") (pin "1") (pinfunction "1_1") (pintype "passive"))
    )
    (net (code "119") (name "unconnected-(DD1-OSC_OUT-Pad4)") (class "Default")
      (node (ref "DD1") (pin "4") (pinfunction "OSC_OUT_4") (pintype "passive"))
    )
    (net (code "120") (name "unconnected-(DD1-RT-Pad6)") (class "Default")
      (node (ref "DD1") (pin "6") (pinfunction "RT_6") (pintype "passive"))
    )
    (net (code "121") (name "unconnected-(DD4-OSC_OUT-Pad4)") (class "Default")
      (node (ref "DD4") (pin "4") (pinfunction "OSC_OUT_4") (pintype "passive"))
    )
    (net (code "122") (name "unconnected-(DD4-RT-Pad6)") (class "Default")
      (node (ref "DD4") (pin "6") (pinfunction "RT_6") (pintype "passive"))
    )
    (net (code "123") (name "unconnected-(U6-VIA-Pad3)") (class "Default")
      (node (ref "U6") (pin "3") (pinfunction "VIA_3") (pintype "input"))
    )
    (net (code "124") (name "unconnected-(U6-VOA-Pad14)") (class "Default")
      (node (ref "U6") (pin "14") (pinfunction "VOA_14") (pintype "tri_state"))
    )
    (net (code "125") (name "unconnected-(X4-Pad4)") (class "Default")
      (node (ref "X4") (pin "4") (pinfunction "4_4") (pintype "passive"))
    )
  )
)
